# Tractive_System_Board_Rev7_Test.net
KiCad netlist of a schematic drawn in EAGLE
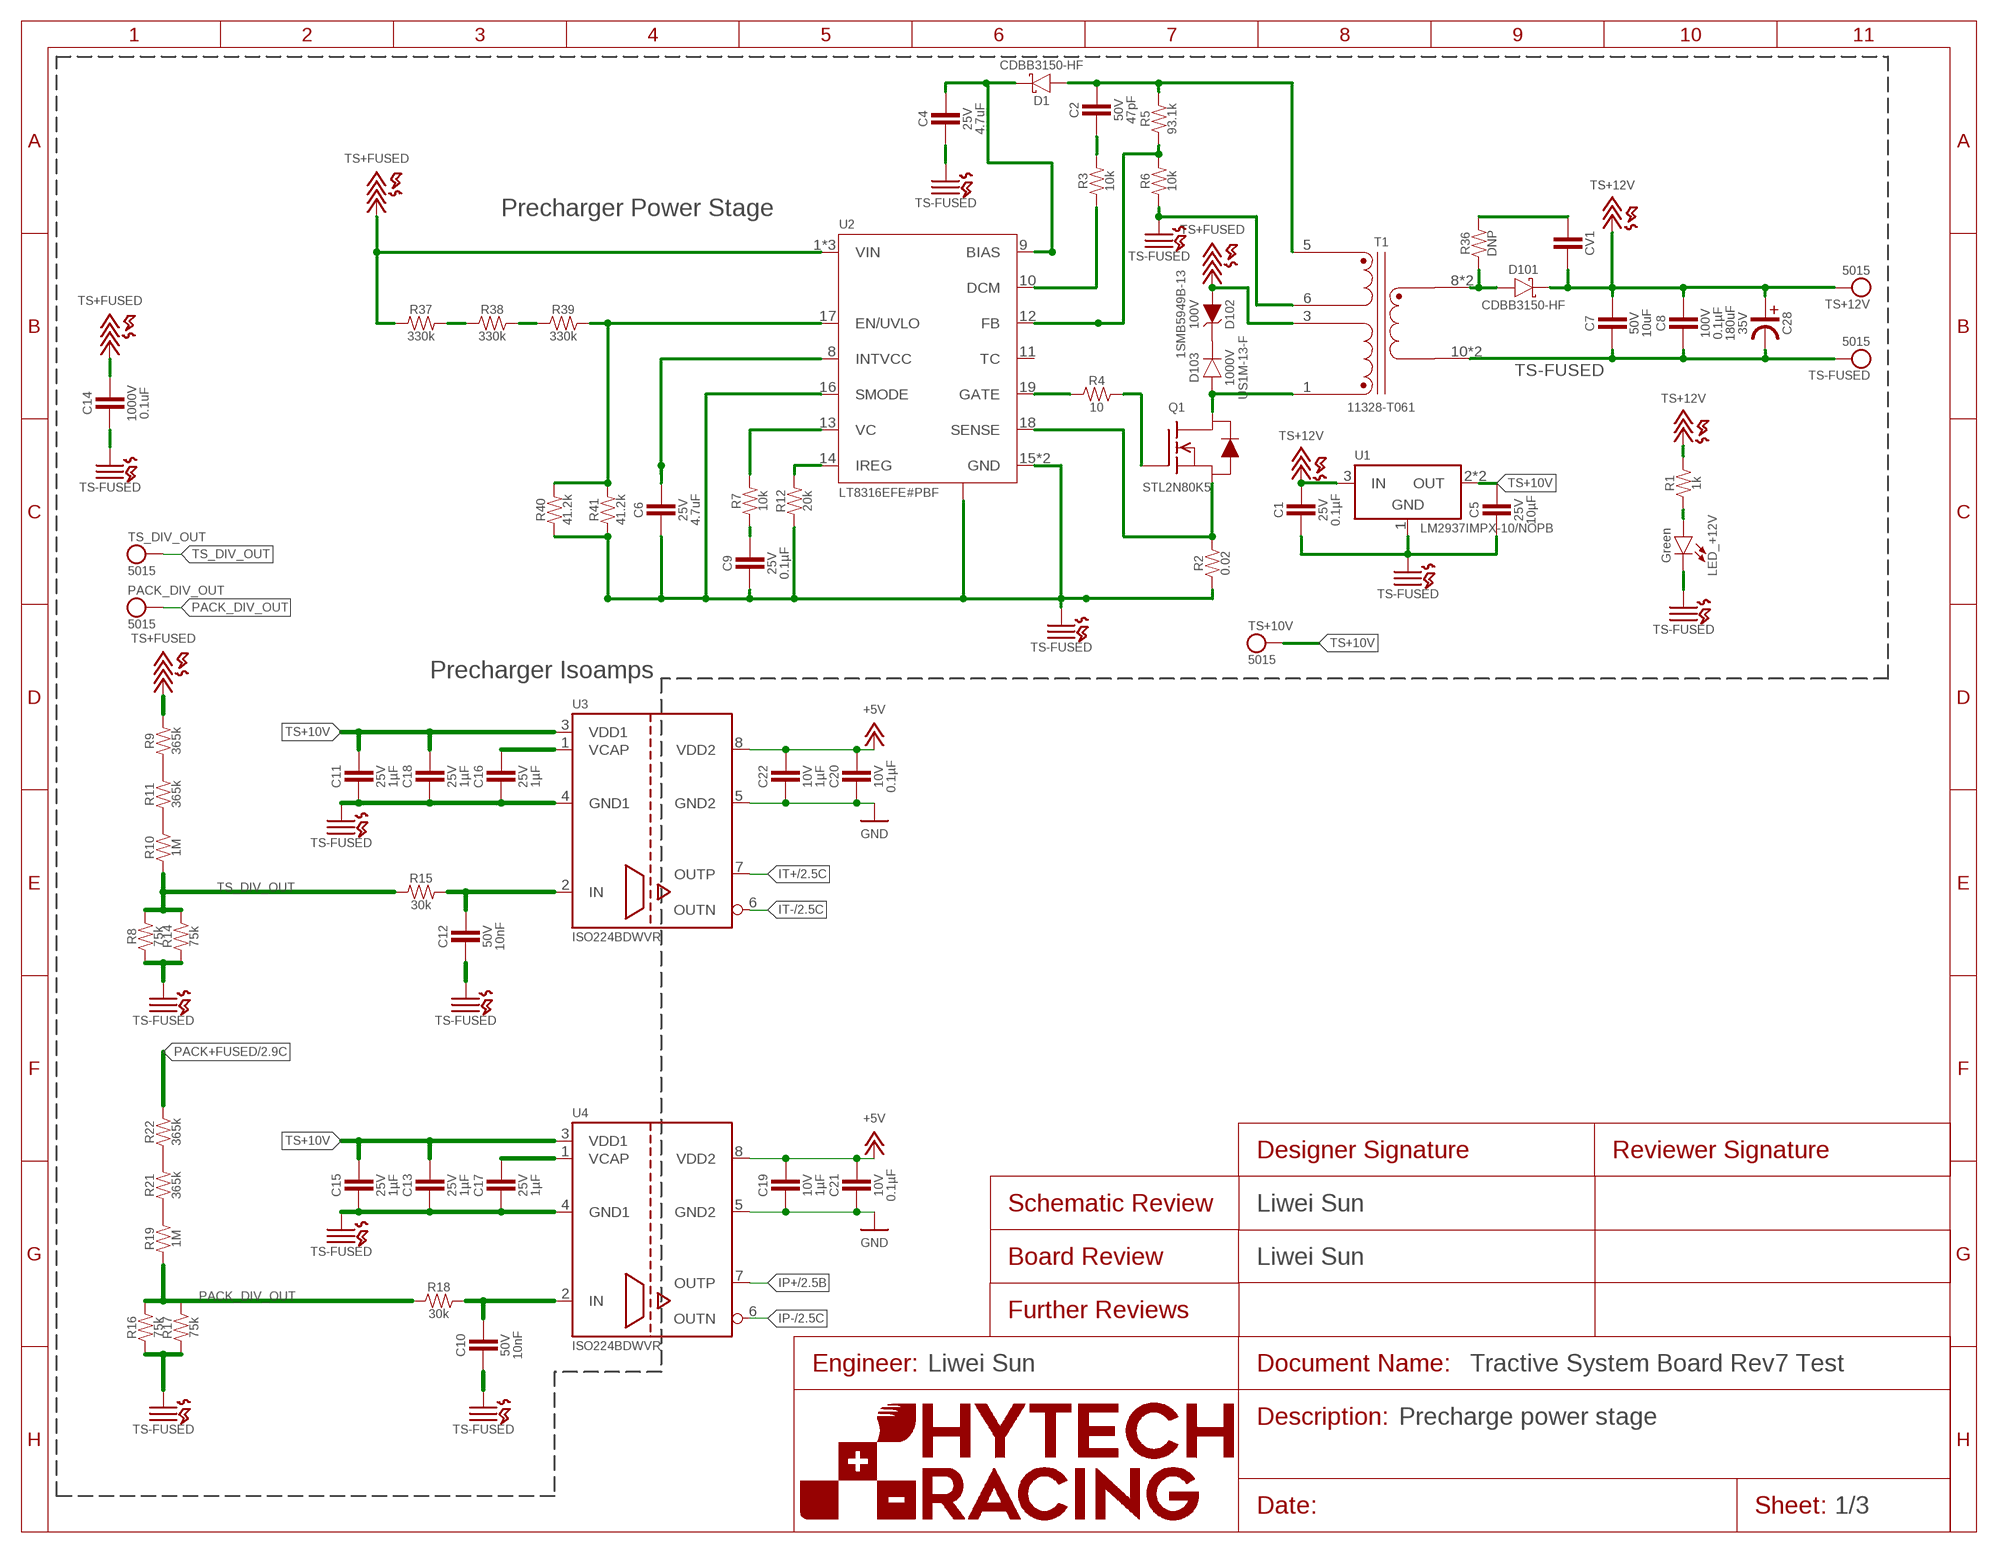
[diagram p0: schematic, sheet 1]
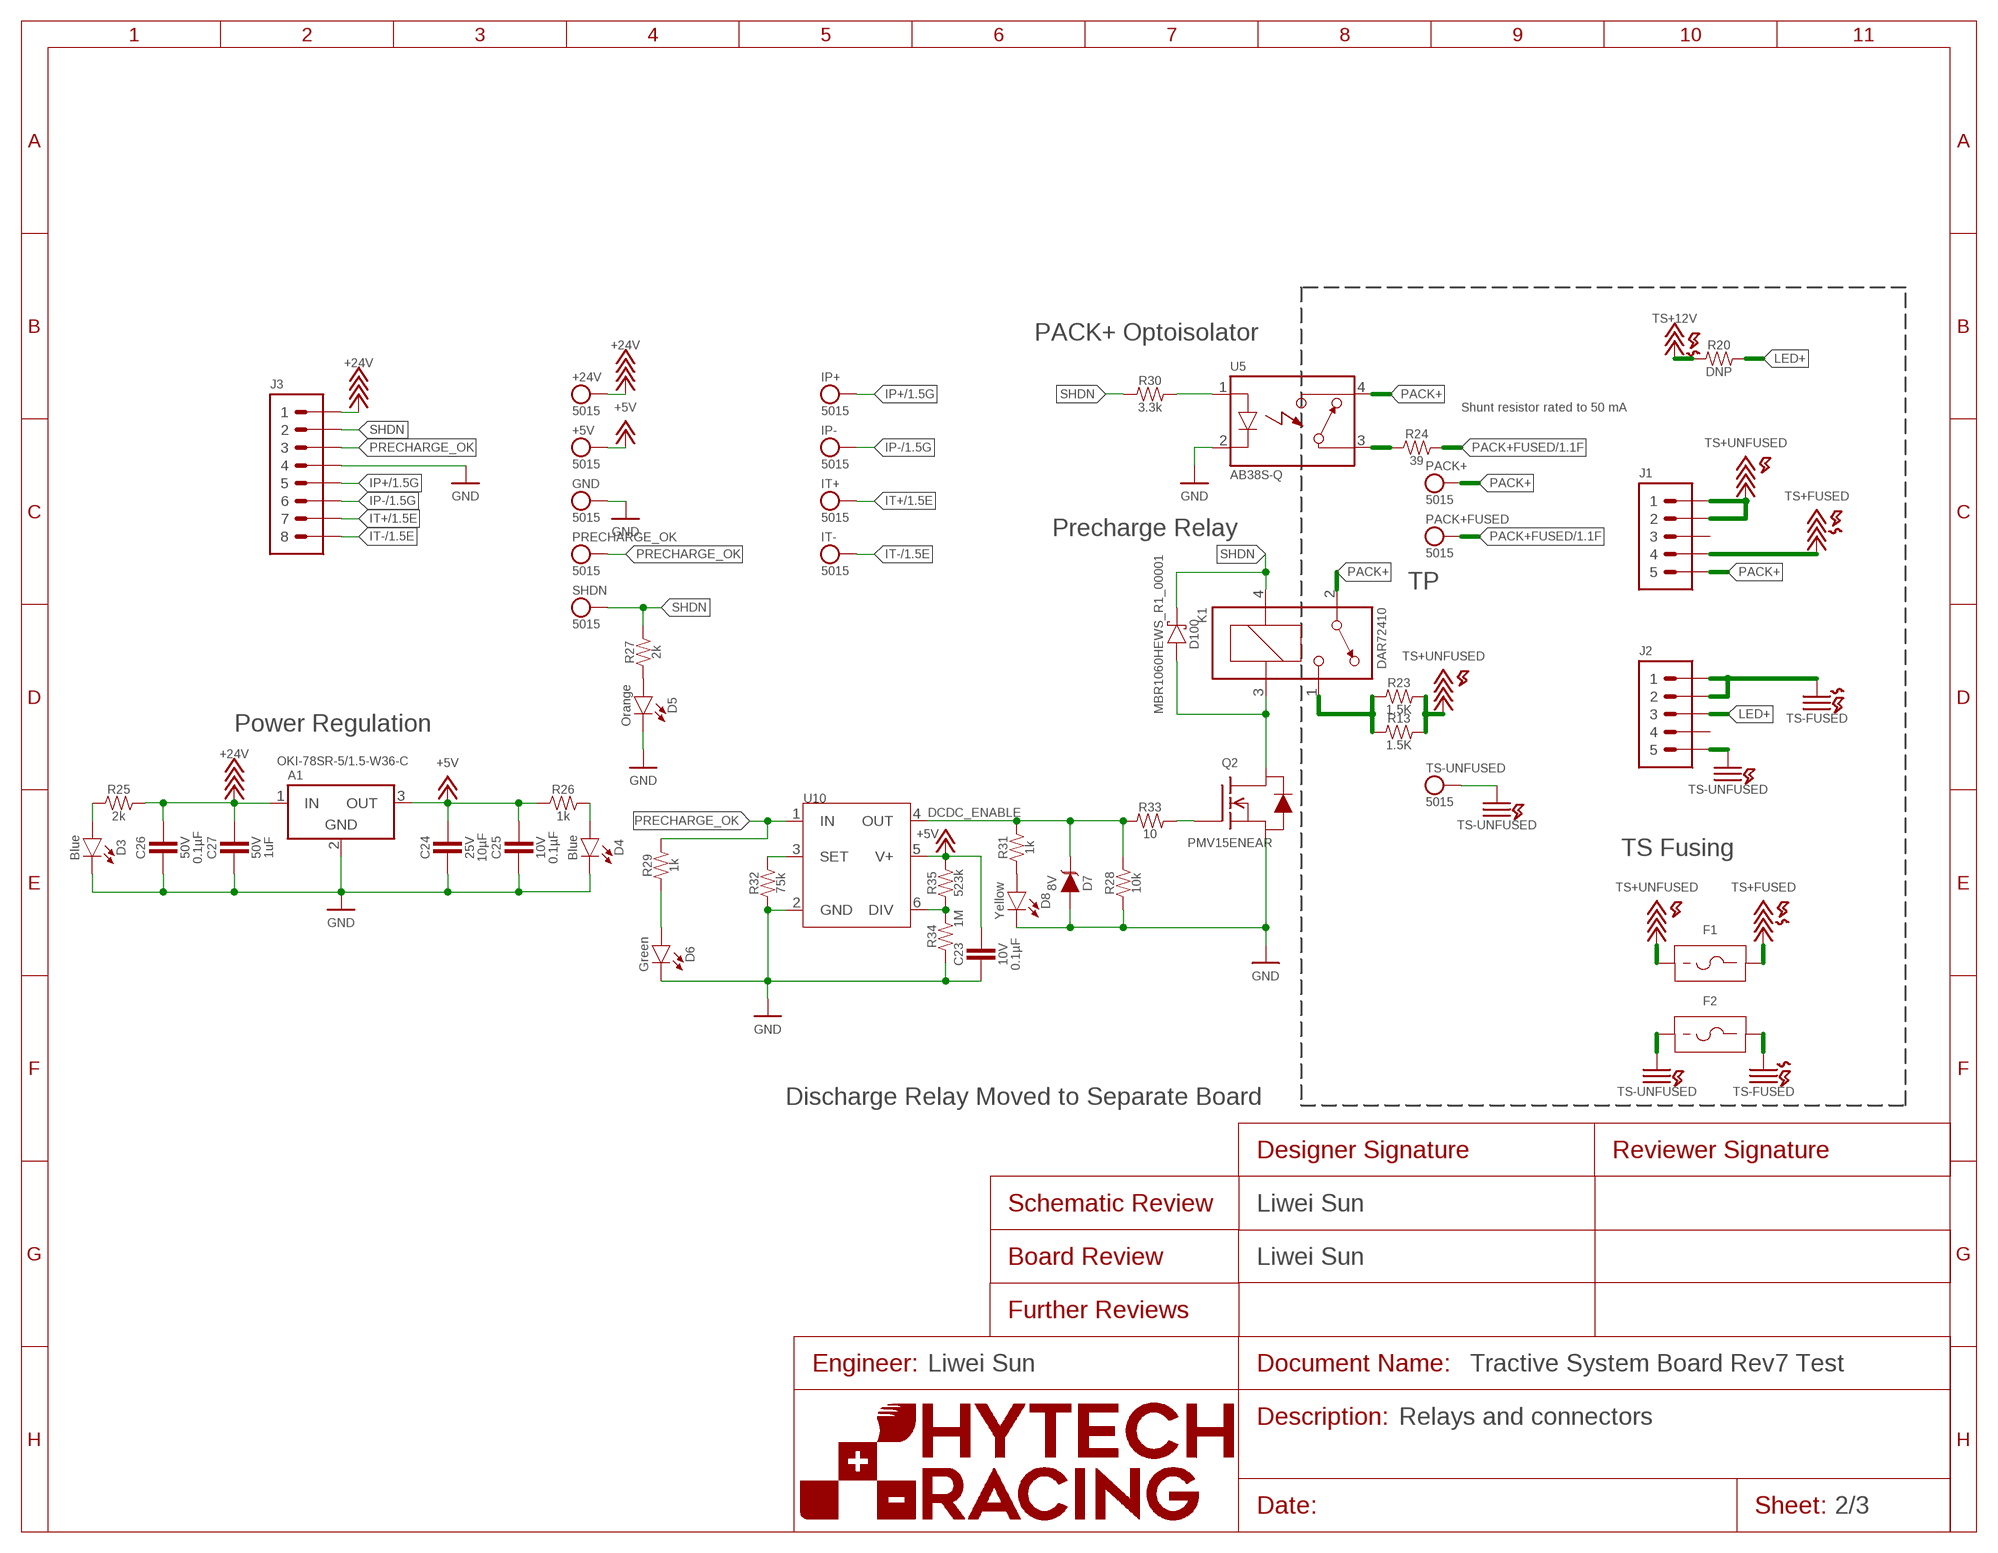
[diagram p1: schematic, sheet 2]
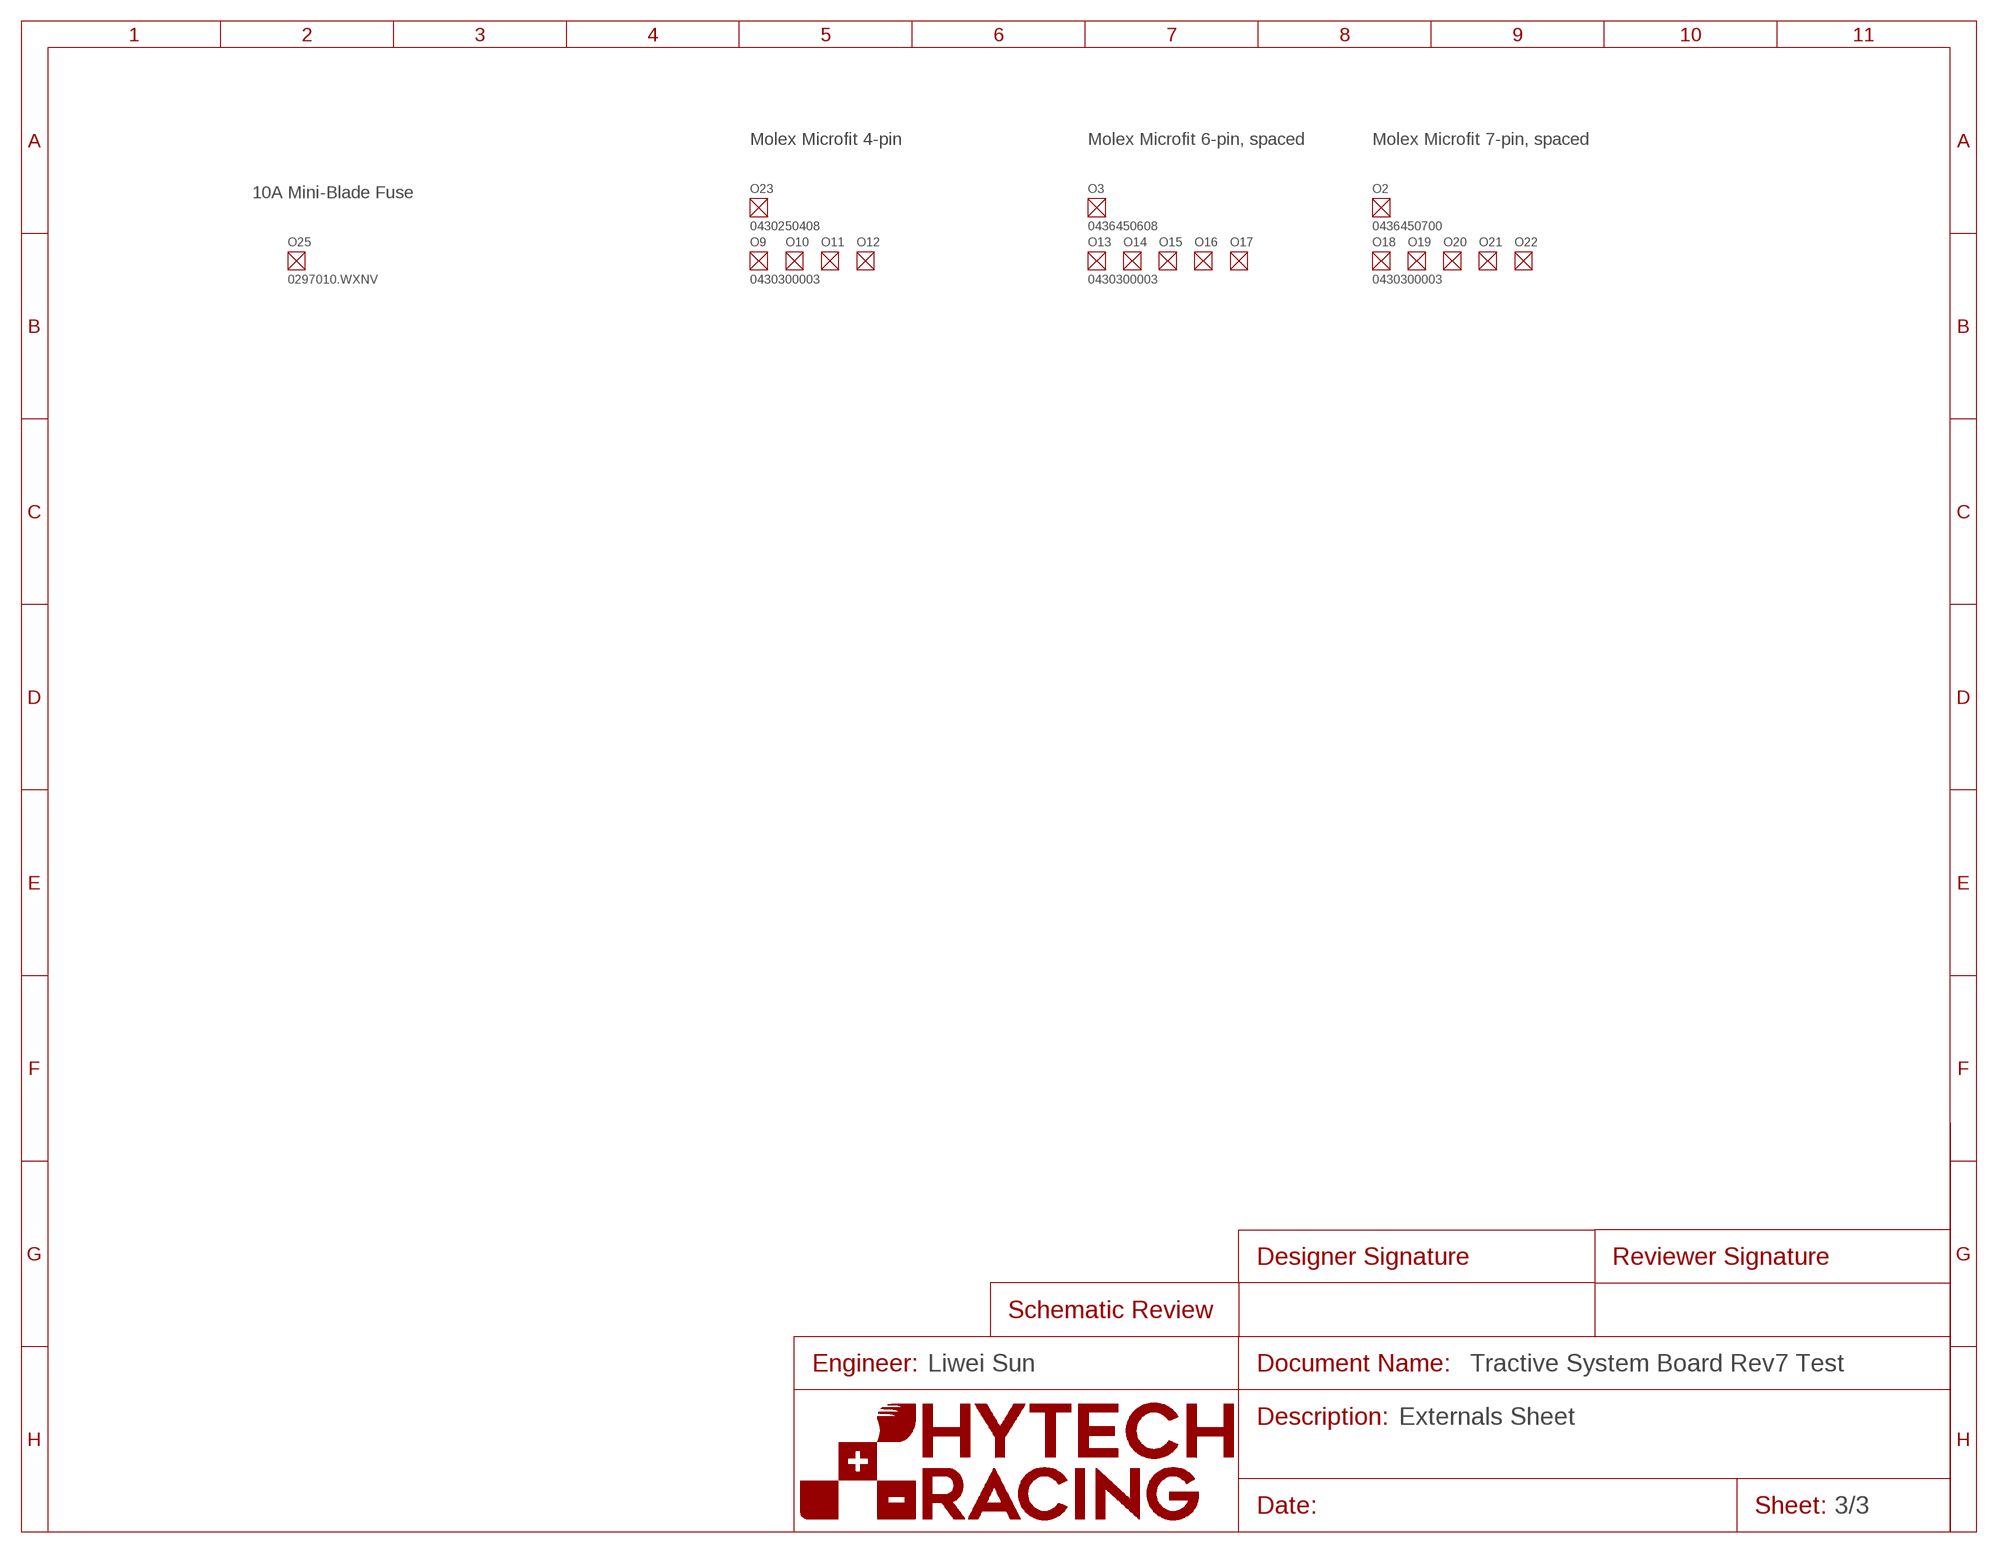
[diagram p2: schematic, sheet 3]

(export (version "E")
  (design (tool "Eeschema 10.0.6"))
  (components
    (comp (ref "+5V")
      (value "TEST_POINT")
      (footprint "eagle-import:5015")
      (fields (field (name "MPN") "5015") (field (name "MANUFACTURER") "Keystone Electronics"))
      (libsource (lib "eagle-import") (part "TEST_POINT"))
    )
    (comp (ref "+24V")
      (value "TEST_POINT")
      (footprint "eagle-import:5015")
      (fields (field (name "MPN") "5015") (field (name "MANUFACTURER") "Keystone Electronics"))
      (libsource (lib "eagle-import") (part "TEST_POINT"))
    )
    (comp (ref "A1")
      (value "VOLTAGE_REGULATOR_MODULE_OKI-78SR_5V")
      (footprint "eagle-import:OKI-78SR")
      (fields
        (field (name "MANUFACTURER") "Murata Power Solutions Inc.")
        (field (name "MPN") "OKI-78SR-5/1.5-W36-C")
      )
      (libsource (lib "eagle-import") (part "VOLTAGE_REGULATOR_MODULE_?_OKI-78SR5V"))
    )
    (comp (ref "C23")
      (value "CAPACITOR_0603_10V_0.1UF")
      (footprint "eagle-import:0603-CAP")
      (fields
        (field (name "CAPACITANCE") "0.1µF")
        (field (name "MANUFACTURER") "Vishay Vitramon")
        (field (name "MPN") "VJ0603Y104JXQPW1BC")
        (field (name "TOLERANCE") "5%")
        (field (name "VOLTAGE") "10V")
      )
      (libsource (lib "eagle-import") (part "CAPACITOR_?_060310V_0.1UF"))
    )
    (comp (ref "C24")
      (value "CAPACITOR_0603_25V_10UF")
      (footprint "eagle-import:0603-CAP")
      (fields
        (field (name "CAPACITANCE") "10µF")
        (field (name "MANUFACTURER") "Murata Electronics")
        (field (name "MPN") "GRM188R61E106MA73D")
        (field (name "TOLERANCE") "20%")
        (field (name "VOLTAGE") "25V")
      )
      (libsource (lib "eagle-import") (part "CAPACITOR_?_060325V_10UF"))
    )
    (comp (ref "C25")
      (value "CAPACITOR_0603_10V_0.1UF")
      (footprint "eagle-import:0603-CAP")
      (fields
        (field (name "CAPACITANCE") "0.1µF")
        (field (name "MANUFACTURER") "Vishay Vitramon")
        (field (name "MPN") "VJ0603Y104JXQPW1BC")
        (field (name "TOLERANCE") "5%")
        (field (name "VOLTAGE") "10V")
      )
      (libsource (lib "eagle-import") (part "CAPACITOR_?_060310V_0.1UF"))
    )
    (comp (ref "C26")
      (value "CAPACITOR_0603_50V_0.1UF")
      (footprint "eagle-import:0603-CAP")
      (fields
        (field (name "CAPACITANCE") "0.1µF")
        (field (name "MANUFACTURER") "Yageo")
        (field (name "MPN") "CC0603KRX7R9BB104")
        (field (name "TOLERANCE") "10%")
        (field (name "VOLTAGE") "50V")
      )
      (libsource (lib "eagle-import") (part "CAPACITOR_?_060350V_0.1UF"))
    )
    (comp (ref "C27")
      (value "CAPACITOR_0603_50V_1UF")
      (footprint "eagle-import:0603-CAP")
      (fields
        (field (name "CAPACITANCE") "1uF")
        (field (name "MANUFACTURER") "Taiyo Yuden")
        (field (name "MPN") "UMK107BJ105KA-T")
        (field (name "TOLERANCE") "10%")
        (field (name "VOLTAGE") "50V")
      )
      (libsource (lib "eagle-import") (part "CAPACITOR_?_060350V_1UF"))
    )
    (comp (ref "D3")
      (value "LED_0603_BLUE")
      (footprint "eagle-import:0603-LED")
      (fields
        (field (name "COLOR") "Blue")
        (field (name "MANUFACTURER") "Kingbright")
        (field (name "MPN") "APT1608VBC/D")
      )
      (libsource (lib "eagle-import") (part "LED_?_0603BLUE"))
    )
    (comp (ref "D4")
      (value "LED_0603_BLUE")
      (footprint "eagle-import:0603-LED")
      (fields
        (field (name "COLOR") "Blue")
        (field (name "MANUFACTURER") "Kingbright")
        (field (name "MPN") "APT1608VBC/D")
      )
      (libsource (lib "eagle-import") (part "LED_?_0603BLUE"))
    )
    (comp (ref "D5")
      (value "LED_0603_ORANGE")
      (footprint "eagle-import:0603-LED")
      (fields
        (field (name "COLOR") "Orange")
        (field (name "MANUFACTURER") "Kingbright")
        (field (name "MPN") "APT1608SECK")
      )
      (libsource (lib "eagle-import") (part "LED_?_0603ORANGE"))
    )
    (comp (ref "D6")
      (value "LED_0603_GREEN")
      (footprint "eagle-import:0603-LED")
      (fields
        (field (name "COLOR") "Green")
        (field (name "MANUFACTURER") "Kingbright")
        (field (name "MPN") "APT1608ZGCK")
      )
      (libsource (lib "eagle-import") (part "LED_?_0603GREEN"))
    )
    (comp (ref "D7")
      (value "TVS__8V")
      (footprint "eagle-import:SOT-23")
      (fields
        (field (name "MANUFACTURER") "Vishay General Semiconductor - Diodes Division")
        (field (name "MPN") "GSOT08-E3-08")
        (field (name "VOLTAGE") "8V")
      )
      (libsource (lib "eagle-import") (part "TVS_?_8V"))
    )
    (comp (ref "D8")
      (value "LED_0603_YELLOW")
      (footprint "eagle-import:0603-LED")
      (fields
        (field (name "COLOR") "Yellow")
        (field (name "MANUFACTURER") "Kingbright")
        (field (name "MPN") "APT1608SYCK/J3-PRV")
      )
      (libsource (lib "eagle-import") (part "LED_?_0603YELLOW"))
    )
    (comp (ref "D100")
      (value "SCHOTTKY_SOD323_60V")
      (footprint "eagle-import:SOD-323")
      (fields
        (field (name "MANUFACTURER") "Panjit International Inc.")
        (field (name "MPN") "MBR1060HEWS_R1_00001")
        (field (name "VOLTAGE") "60V")
      )
      (libsource (lib "eagle-import") (part "SCHOTTKY_?_SOD32360V"))
    )
    (comp (ref "F1")
      (value "FUSE_HOLDER_122")
      (footprint "eagle-import:122")
      (fields (field (name "MPN") "01220088Z") (field (name "MANUFACTURER") "Littelfuse"))
      (libsource (lib "eagle-import") (part "FUSE_HOLDER_122"))
    )
    (comp (ref "F2")
      (value "FUSE_HOLDER_122")
      (footprint "eagle-import:122")
      (fields (field (name "MPN") "01220088Z") (field (name "MANUFACTURER") "Littelfuse"))
      (libsource (lib "eagle-import") (part "FUSE_HOLDER_122"))
    )
    (comp (ref "GND")
      (value "TEST_POINT")
      (footprint "eagle-import:5015")
      (fields (field (name "MPN") "5015") (field (name "MANUFACTURER") "Keystone Electronics"))
      (libsource (lib "eagle-import") (part "TEST_POINT"))
    )
    (comp (ref "IP+")
      (value "TEST_POINT")
      (footprint "eagle-import:5015")
      (fields (field (name "MPN") "5015") (field (name "MANUFACTURER") "Keystone Electronics"))
      (libsource (lib "eagle-import") (part "TEST_POINT"))
    )
    (comp (ref "IP-")
      (value "TEST_POINT")
      (footprint "eagle-import:5015")
      (fields (field (name "MPN") "5015") (field (name "MANUFACTURER") "Keystone Electronics"))
      (libsource (lib "eagle-import") (part "TEST_POINT"))
    )
    (comp (ref "IT+")
      (value "TEST_POINT")
      (footprint "eagle-import:5015")
      (fields (field (name "MPN") "5015") (field (name "MANUFACTURER") "Keystone Electronics"))
      (libsource (lib "eagle-import") (part "TEST_POINT"))
    )
    (comp (ref "IT-")
      (value "TEST_POINT")
      (footprint "eagle-import:5015")
      (fields (field (name "MPN") "5015") (field (name "MANUFACTURER") "Keystone Electronics"))
      (libsource (lib "eagle-import") (part "TEST_POINT"))
    )
    (comp (ref "J1")
      (value "CONNECTOR-5_MICRO_V7S_")
      (footprint "eagle-import:MOLEX_MICROFIT_PTH_VERTICAL_07_SINGLE_SPACED")
      (fields (field (name "MPN") "2165713007") (field (name "MANUFACTURER") "Molex"))
      (libsource (lib "eagle-import") (part "CONNECTOR-5_?_MICRO_V7S"))
    )
    (comp (ref "J2")
      (value "CONNECTOR-5_MICRO_V6S_")
      (footprint "eagle-import:MOLEX_MICROFIT_PTH_VERTICAL_06_SINGLE_SPACED")
      (fields (field (name "MPN") "2165713006") (field (name "MANUFACTURER") "Molex"))
      (libsource (lib "eagle-import") (part "CONNECTOR-5_?_MICRO_V6S"))
    )
    (comp (ref "J3")
      (value "CONNECTOR-8_μF_T_V_BLACK")
      (footprint "eagle-import:MOLEX_MICROFIT_PTH_VERTICAL_08_DUAL")
      (fields (field (name "MANUFACTURER") "Molex") (field (name "MPN") "430450814"))
      (libsource (lib "eagle-import") (part "CONNECTOR-8_?_μF_T_VBLACK"))
    )
    (comp (ref "K1")
      (value "RELAY_SPST_NO_D_24")
      (footprint "eagle-import:D")
      (fields (field (name "MANUFACTURER") "Sensata-Cynergy3") (field (name "MPN") "DAR72410"))
      (libsource (lib "eagle-import") (part "RELAY_SPST_NO_?D_24"))
    )
    (comp (ref "PACK+")
      (value "TEST_POINT")
      (footprint "eagle-import:5015")
      (fields (field (name "MPN") "5015") (field (name "MANUFACTURER") "Keystone Electronics"))
      (libsource (lib "eagle-import") (part "TEST_POINT"))
    )
    (comp (ref "PACK+FUSED")
      (value "TEST_POINT")
      (footprint "eagle-import:5015")
      (fields (field (name "MPN") "5015") (field (name "MANUFACTURER") "Keystone Electronics"))
      (libsource (lib "eagle-import") (part "TEST_POINT"))
    )
    (comp (ref "PRECHARGE_OK")
      (value "TEST_POINT")
      (footprint "eagle-import:5015")
      (fields (field (name "MPN") "5015") (field (name "MANUFACTURER") "Keystone Electronics"))
      (libsource (lib "eagle-import") (part "TEST_POINT"))
    )
    (comp (ref "Q2")
      (value "TRANSISTOR_N_MOS__PMV15ENEA")
      (footprint "eagle-import:SOT-23")
      (fields (field (name "MANUFACTURER") "Nexperia USA Inc.") (field (name "MPN") "PMV15ENEAR"))
      (libsource (lib "eagle-import") (part "TRANSISTOR_N_MOS_?_PMV15ENEA"))
    )
    (comp (ref "R13")
      (value "RESISTOR_B20-SHORTENED_1.5K")
      (footprint "eagle-import:B20-SHORTENED")
      (fields
        (field (name "MANUFACTURER") "Ohmite")
        (field (name "MPN") "B20J1K5E")
        (field (name "POWER") "20W")
        (field (name "RESISTANCE") "1.5K")
      )
      (libsource (lib "eagle-import") (part "RESISTOR_?_B20-SHORTENED1.5K"))
    )
    (comp (ref "R20")
      (value "RESISTOR_0603_DNP")
      (footprint "eagle-import:0603-RES")
      (fields (field (name "RESISTANCE") "DNP"))
      (libsource (lib "eagle-import") (part "RESISTOR_?_0603DNP"))
    )
    (comp (ref "R23")
      (value "RESISTOR_B20-SHORTENED_1.5K")
      (footprint "eagle-import:B20-SHORTENED")
      (fields
        (field (name "MANUFACTURER") "Ohmite")
        (field (name "MPN") "B20J1K5E")
        (field (name "POWER") "20W")
        (field (name "RESISTANCE") "1.5K")
      )
      (libsource (lib "eagle-import") (part "RESISTOR_?_B20-SHORTENED1.5K"))
    )
    (comp (ref "R24")
      (value "RESISTOR_0603_39")
      (footprint "eagle-import:0603-RES")
      (fields
        (field (name "MANUFACTURER") "Yageo")
        (field (name "MPN") "RT0603BRD0739RL")
        (field (name "POWER") "0.1W")
        (field (name "RESISTANCE") "39")
      )
      (libsource (lib "eagle-import") (part "RESISTOR_?_060339"))
    )
    (comp (ref "R25")
      (value "RESISTOR_0603_2K")
      (footprint "eagle-import:0603-RES")
      (fields
        (field (name "MANUFACTURER") "Panasonic Electronic Components")
        (field (name "MPN") "ERJ-UP3F2001V")
        (field (name "POWER") "0.25W")
        (field (name "RESISTANCE") "2k")
      )
      (libsource (lib "eagle-import") (part "RESISTOR_?_06032K"))
    )
    (comp (ref "R26")
      (value "RESISTOR_0603_1K")
      (footprint "eagle-import:0603-RES")
      (fields
        (field (name "MANUFACTURER") "TE Connectivity Passive Product")
        (field (name "MPN") " CPF-A-0603B1K0E")
        (field (name "POWER") "0.0625W")
        (field (name "RESISTANCE") "1k")
      )
      (libsource (lib "eagle-import") (part "RESISTOR_?_06031K"))
    )
    (comp (ref "R27")
      (value "RESISTOR_0603_2K")
      (footprint "eagle-import:0603-RES")
      (fields
        (field (name "MANUFACTURER") "Panasonic Electronic Components")
        (field (name "MPN") "ERJ-UP3F2001V")
        (field (name "POWER") "0.25W")
        (field (name "RESISTANCE") "2k")
      )
      (libsource (lib "eagle-import") (part "RESISTOR_?_06032K"))
    )
    (comp (ref "R28")
      (value "RESISTOR_0603_10K")
      (footprint "eagle-import:0603-RES")
      (fields
        (field (name "MANUFACTURER") "Panasonic Electronic Components")
        (field (name "MPN") "ERA-3ARB103V")
        (field (name "POWER") "0.1W")
        (field (name "RESISTANCE") "10k")
      )
      (libsource (lib "eagle-import") (part "RESISTOR_?_060310K"))
    )
    (comp (ref "R29")
      (value "RESISTOR_0603_1K")
      (footprint "eagle-import:0603-RES")
      (fields
        (field (name "MANUFACTURER") "TE Connectivity Passive Product")
        (field (name "MPN") " CPF-A-0603B1K0E")
        (field (name "POWER") "0.0625W")
        (field (name "RESISTANCE") "1k")
      )
      (libsource (lib "eagle-import") (part "RESISTOR_?_06031K"))
    )
    (comp (ref "R30")
      (value "RESISTOR_0603_3.3K")
      (footprint "eagle-import:0603-RES")
      (fields
        (field (name "MANUFACTURER") "Panasonic Electronic Components")
        (field (name "MPN") "ERJ-PB3D3301V")
        (field (name "POWER") "0.3W")
        (field (name "RESISTANCE") "3.3k")
      )
      (libsource (lib "eagle-import") (part "RESISTOR_?_06033.3K"))
    )
    (comp (ref "R31")
      (value "RESISTOR_0603_1K")
      (footprint "eagle-import:0603-RES")
      (fields
        (field (name "MANUFACTURER") "TE Connectivity Passive Product")
        (field (name "MPN") " CPF-A-0603B1K0E")
        (field (name "POWER") "0.0625W")
        (field (name "RESISTANCE") "1k")
      )
      (libsource (lib "eagle-import") (part "RESISTOR_?_06031K"))
    )
    (comp (ref "R32")
      (value "RESISTOR_0603_75K")
      (footprint "eagle-import:0603-RES")
      (fields
        (field (name "MANUFACTURER") "Yageo")
        (field (name "MPN") "RT0603BRE0775KL")
        (field (name "POWER") "0.1W")
        (field (name "RESISTANCE") "75k")
      )
      (libsource (lib "eagle-import") (part "RESISTOR_?_060375K"))
    )
    (comp (ref "R33")
      (value "RESISTOR_0603_10")
      (footprint "eagle-import:0603-RES")
      (fields
        (field (name "MANUFACTURER") "Yageo")
        (field (name "MPN") "RC0603FR-0710RL")
        (field (name "POWER") "0.1W")
        (field (name "RESISTANCE") "10")
      )
      (libsource (lib "eagle-import") (part "RESISTOR_?_060310"))
    )
    (comp (ref "R34")
      (value "RESISTOR_0805_1M")
      (footprint "eagle-import:0805-RES")
      (fields
        (field (name "MANUFACTURER") "Panasonic Electronic Components")
        (field (name "MPN") "ERJ-PB6B1004V")
        (field (name "POWER") "0.25W")
        (field (name "RESISTANCE") "1M")
      )
      (libsource (lib "eagle-import") (part "RESISTOR_?_08051M"))
    )
    (comp (ref "R35")
      (value "RESISTOR_0805_523K")
      (footprint "eagle-import:0805-RES")
      (fields
        (field (name "MANUFACTURER") "Panasonic Electronic Components")
        (field (name "MPN") "ERJ-PB6B5233V")
        (field (name "POWER") "0.25W")
        (field (name "RESISTANCE") "523k")
      )
      (libsource (lib "eagle-import") (part "RESISTOR_?_0805523K"))
    )
    (comp (ref "SHDN")
      (value "TEST_POINT")
      (footprint "eagle-import:5015")
      (fields (field (name "MPN") "5015") (field (name "MANUFACTURER") "Keystone Electronics"))
      (libsource (lib "eagle-import") (part "TEST_POINT"))
    )
    (comp (ref "TS-UNFUSED")
      (value "TEST_POINT")
      (footprint "eagle-import:5015")
      (fields (field (name "MPN") "5015") (field (name "MANUFACTURER") "Keystone Electronics"))
      (libsource (lib "eagle-import") (part "TEST_POINT"))
    )
    (comp (ref "U5")
      (value "RELAY_SOLIDSTATE_NO_AB38S-Q-AIRGAP")
      (footprint "eagle-import:SOP-04-AIRGAP")
      (fields
        (field (name "MPN") "AB38S-Q")
        (field (name "MANUFACTURER") "Comus International")
        (field (name "VOLTAGE") "600V")
      )
      (libsource (lib "eagle-import") (part "RELAY_SOLIDSTATE_NO_AB38S-Q-AIRGAP"))
    )
    (comp (ref "U10")
      (value "LTC6994-2")
      (footprint "eagle-import:SOT-23-6")
      (libsource (lib "eagle-import") (part "LTC6994-2"))
    )
    (comp (ref "C1")
      (value "CAPACITOR_0603_25V_0.1UF")
      (footprint "eagle-import:0603-CAP")
      (fields
        (field (name "CAPACITANCE") "0.1µF")
        (field (name "MANUFACTURER") "Samsung Electro-Mechanics")
        (field (name "MPN") "CL10B104KA8NNNC")
        (field (name "TOLERANCE") "10%")
        (field (name "VOLTAGE") "25V")
      )
      (libsource (lib "eagle-import") (part "CAPACITOR_?_060325V_0.1UF"))
    )
    (comp (ref "C2")
      (value "CAPACITOR_0603_50V_47PF")
      (footprint "eagle-import:0603-CAP")
      (fields
        (field (name "CAPACITANCE") "47pF")
        (field (name "MANUFACTURER") "TDK Corporation")
        (field (name "MPN") "CGA3E2NP01H470J080AA")
        (field (name "TOLERANCE") "5%")
        (field (name "VOLTAGE") "50V")
      )
      (libsource (lib "eagle-import") (part "CAPACITOR_?_060350V_47PF"))
    )
    (comp (ref "C4")
      (value "CAPACITOR_0603_25V_4.7UF")
      (footprint "eagle-import:0603-CAP")
      (fields
        (field (name "CAPACITANCE") "4.7uF")
        (field (name "MANUFACTURER") "TDK Corporation")
        (field (name "MPN") " C1608X5R1E475K080AC")
        (field (name "TOLERANCE") "10%")
        (field (name "VOLTAGE") "25V")
      )
      (libsource (lib "eagle-import") (part "CAPACITOR_?_060325V_4.7UF"))
    )
    (comp (ref "C5")
      (value "CAPACITOR_0603_25V_10UF")
      (footprint "eagle-import:0603-CAP")
      (fields
        (field (name "CAPACITANCE") "10µF")
        (field (name "MANUFACTURER") "Murata Electronics")
        (field (name "MPN") "GRM188R61E106MA73D")
        (field (name "TOLERANCE") "20%")
        (field (name "VOLTAGE") "25V")
      )
      (libsource (lib "eagle-import") (part "CAPACITOR_?_060325V_10UF"))
    )
    (comp (ref "C6")
      (value "CAPACITOR_0603_25V_4.7UF")
      (footprint "eagle-import:0603-CAP")
      (fields
        (field (name "CAPACITANCE") "4.7uF")
        (field (name "MANUFACTURER") "TDK Corporation")
        (field (name "MPN") " C1608X5R1E475K080AC")
        (field (name "TOLERANCE") "10%")
        (field (name "VOLTAGE") "25V")
      )
      (libsource (lib "eagle-import") (part "CAPACITOR_?_060325V_4.7UF"))
    )
    (comp (ref "C7")
      (value "CAPACITOR_0805_50V_10UF")
      (footprint "eagle-import:0805-CAP")
      (fields
        (field (name "CAPACITANCE") "10uF")
        (field (name "MANUFACTURER") "Murata")
        (field (name "MPN") " GRM21BR61H106KE43L")
        (field (name "TOLERANCE") "10%")
        (field (name "VOLTAGE") "50V")
      )
      (libsource (lib "eagle-import") (part "CAPACITOR_?_080550V_10UF"))
    )
    (comp (ref "C8")
      (value "CAPACITOR_0603_100V_0.1UF")
      (footprint "eagle-import:0603-CAP")
      (fields
        (field (name "CAPACITANCE") "0.1µF")
        (field (name "MANUFACTURER") "Yageo")
        (field (name "MPN") "CC0603KRX7R0BB104")
        (field (name "TOLERANCE") "10%")
        (field (name "VOLTAGE") "100V")
      )
      (libsource (lib "eagle-import") (part "CAPACITOR_?_0603100V_0.1UF"))
    )
    (comp (ref "C9")
      (value "CAPACITOR_0603_25V_0.1UF")
      (footprint "eagle-import:0603-CAP")
      (fields
        (field (name "CAPACITANCE") "0.1µF")
        (field (name "MANUFACTURER") "Samsung Electro-Mechanics")
        (field (name "MPN") "CL10B104KA8NNNC")
        (field (name "TOLERANCE") "10%")
        (field (name "VOLTAGE") "25V")
      )
      (libsource (lib "eagle-import") (part "CAPACITOR_?_060325V_0.1UF"))
    )
    (comp (ref "C10")
      (value "CAPACITOR_0603_50V_10NF")
      (footprint "eagle-import:0603-CAP")
      (fields
        (field (name "CAPACITANCE") "10nF")
        (field (name "MANUFACTURER") "TDK Corporation")
        (field (name "MPN") "C1608C0G1H103J080AA")
        (field (name "TOLERANCE") "5%")
        (field (name "VOLTAGE") "50V")
      )
      (libsource (lib "eagle-import") (part "CAPACITOR_?_060350V_10NF"))
    )
    (comp (ref "C11")
      (value "CAPACITOR_0603_25V_1UF")
      (footprint "eagle-import:0603-CAP")
      (fields
        (field (name "CAPACITANCE") "1µF")
        (field (name "MANUFACTURER") "Samsung Electro-Mechanics")
        (field (name "MPN") "CL10B105KA8NNNC")
        (field (name "TOLERANCE") "10%")
        (field (name "VOLTAGE") "25V")
      )
      (libsource (lib "eagle-import") (part "CAPACITOR_?_060325V_1UF"))
    )
    (comp (ref "C12")
      (value "CAPACITOR_0603_50V_10NF")
      (footprint "eagle-import:0603-CAP")
      (fields
        (field (name "CAPACITANCE") "10nF")
        (field (name "MANUFACTURER") "TDK Corporation")
        (field (name "MPN") "C1608C0G1H103J080AA")
        (field (name "TOLERANCE") "5%")
        (field (name "VOLTAGE") "50V")
      )
      (libsource (lib "eagle-import") (part "CAPACITOR_?_060350V_10NF"))
    )
    (comp (ref "C13")
      (value "CAPACITOR_0603_25V_1UF")
      (footprint "eagle-import:0603-CAP")
      (fields
        (field (name "CAPACITANCE") "1µF")
        (field (name "MANUFACTURER") "Samsung Electro-Mechanics")
        (field (name "MPN") "CL10B105KA8NNNC")
        (field (name "TOLERANCE") "10%")
        (field (name "VOLTAGE") "25V")
      )
      (libsource (lib "eagle-import") (part "CAPACITOR_?_060325V_1UF"))
    )
    (comp (ref "C14")
      (value "CAPACITOR_1812_1000V_0.1UF")
      (footprint "eagle-import:1812-CAP")
      (fields
        (field (name "CAPACITANCE") "0.1uF")
        (field (name "MANUFACTURER") "KEMET")
        (field (name "MPN") "C1812W104KDRAC7800")
        (field (name "TOLERANCE") "10%")
        (field (name "VOLTAGE") "1000V")
      )
      (libsource (lib "eagle-import") (part "CAPACITOR_?_18121000V_0.1UF"))
    )
    (comp (ref "C15")
      (value "CAPACITOR_0603_25V_1UF")
      (footprint "eagle-import:0603-CAP")
      (fields
        (field (name "CAPACITANCE") "1µF")
        (field (name "MANUFACTURER") "Samsung Electro-Mechanics")
        (field (name "MPN") "CL10B105KA8NNNC")
        (field (name "TOLERANCE") "10%")
        (field (name "VOLTAGE") "25V")
      )
      (libsource (lib "eagle-import") (part "CAPACITOR_?_060325V_1UF"))
    )
    (comp (ref "C16")
      (value "CAPACITOR_0603_25V_1UF")
      (footprint "eagle-import:0603-CAP")
      (fields
        (field (name "CAPACITANCE") "1µF")
        (field (name "MANUFACTURER") "Samsung Electro-Mechanics")
        (field (name "MPN") "CL10B105KA8NNNC")
        (field (name "TOLERANCE") "10%")
        (field (name "VOLTAGE") "25V")
      )
      (libsource (lib "eagle-import") (part "CAPACITOR_?_060325V_1UF"))
    )
    (comp (ref "C17")
      (value "CAPACITOR_0603_25V_1UF")
      (footprint "eagle-import:0603-CAP")
      (fields
        (field (name "CAPACITANCE") "1µF")
        (field (name "MANUFACTURER") "Samsung Electro-Mechanics")
        (field (name "MPN") "CL10B105KA8NNNC")
        (field (name "TOLERANCE") "10%")
        (field (name "VOLTAGE") "25V")
      )
      (libsource (lib "eagle-import") (part "CAPACITOR_?_060325V_1UF"))
    )
    (comp (ref "C18")
      (value "CAPACITOR_0603_25V_1UF")
      (footprint "eagle-import:0603-CAP")
      (fields
        (field (name "CAPACITANCE") "1µF")
        (field (name "MANUFACTURER") "Samsung Electro-Mechanics")
        (field (name "MPN") "CL10B105KA8NNNC")
        (field (name "TOLERANCE") "10%")
        (field (name "VOLTAGE") "25V")
      )
      (libsource (lib "eagle-import") (part "CAPACITOR_?_060325V_1UF"))
    )
    (comp (ref "C19")
      (value "CAPACITOR_0603_10V_1UF")
      (footprint "eagle-import:0603-CAP")
      (fields
        (field (name "CAPACITANCE") "1µF")
        (field (name "MANUFACTURER") "Yageo")
        (field (name "MPN") "CC0603KRX7R6BB105")
        (field (name "TOLERANCE") "10%")
        (field (name "VOLTAGE") "10V")
      )
      (libsource (lib "eagle-import") (part "CAPACITOR_?_060310V_1UF"))
    )
    (comp (ref "C20")
      (value "CAPACITOR_0603_10V_0.1UF")
      (footprint "eagle-import:0603-CAP")
      (fields
        (field (name "CAPACITANCE") "0.1µF")
        (field (name "MANUFACTURER") "Vishay Vitramon")
        (field (name "MPN") "VJ0603Y104JXQPW1BC")
        (field (name "TOLERANCE") "5%")
        (field (name "VOLTAGE") "10V")
      )
      (libsource (lib "eagle-import") (part "CAPACITOR_?_060310V_0.1UF"))
    )
    (comp (ref "C21")
      (value "CAPACITOR_0603_10V_0.1UF")
      (footprint "eagle-import:0603-CAP")
      (fields
        (field (name "CAPACITANCE") "0.1µF")
        (field (name "MANUFACTURER") "Vishay Vitramon")
        (field (name "MPN") "VJ0603Y104JXQPW1BC")
        (field (name "TOLERANCE") "5%")
        (field (name "VOLTAGE") "10V")
      )
      (libsource (lib "eagle-import") (part "CAPACITOR_?_060310V_0.1UF"))
    )
    (comp (ref "C22")
      (value "CAPACITOR_0603_10V_1UF")
      (footprint "eagle-import:0603-CAP")
      (fields
        (field (name "CAPACITANCE") "1µF")
        (field (name "MANUFACTURER") "Yageo")
        (field (name "MPN") "CC0603KRX7R6BB105")
        (field (name "TOLERANCE") "10%")
        (field (name "VOLTAGE") "10V")
      )
      (libsource (lib "eagle-import") (part "CAPACITOR_?_060310V_1UF"))
    )
    (comp (ref "C28")
      (value "CAPACITOR_ELECTROLYTIC_A759KR_180UF")
      (footprint "eagle-import:A759KR")
      (fields
        (field (name "CAPACITANCE") "180uF")
        (field (name "MANUFACTURER") "KEMET")
        (field (name "MPN") "A759KR187M1VAAE024")
        (field (name "TOLERANCE") "20%")
        (field (name "VOLTAGE") "35V")
      )
      (libsource (lib "eagle-import") (part "CAPACITOR_ELECTROLYTIC_?_A759KR180UF"))
    )
    (comp (ref "CV1")
      (value "CAPACITOR_VALUE")
      (footprint "eagle-import:0603-CAP")
      (libsource (lib "eagle-import") (part "CAPACITOR_VALUE"))
    )
    (comp (ref "D1")
      (value "SCHOTTKY_DO-214AA_150V")
      (footprint "eagle-import:DO-214AA")
      (fields
        (field (name "MANUFACTURER") "Comchip Technology")
        (field (name "MPN") "CDBB3150-HF")
        (field (name "VOLTAGE") "150V")
      )
      (libsource (lib "eagle-import") (part "SCHOTTKY_?_DO-214AA150V"))
    )
    (comp (ref "D101")
      (value "SCHOTTKY_DO-214AA_150V")
      (footprint "eagle-import:DO-214AA")
      (fields
        (field (name "MANUFACTURER") "Comchip Technology")
        (field (name "MPN") "CDBB3150-HF")
        (field (name "VOLTAGE") "150V")
      )
      (libsource (lib "eagle-import") (part "SCHOTTKY_?_DO-214AA150V"))
    )
    (comp (ref "D102")
      (value "ZENER_DO-214AA_100V")
      (footprint "eagle-import:DO-214AA")
      (fields
        (field (name "MANUFACTURER") "Diodes Incorporated")
        (field (name "MPN") "1SMB5949B-13")
        (field (name "VOLTAGE") "100V")
      )
      (libsource (lib "eagle-import") (part "ZENER_?_DO-214AA100V"))
    )
    (comp (ref "D103")
      (value "RECTIFIER_1000V_SMA")
      (footprint "eagle-import:SMA")
      (fields
        (field (name "MANUFACTURER") "Diodes Incorporated")
        (field (name "MPN") "US1M-13-F")
        (field (name "VOLTAGE") "1000V")
      )
      (libsource (lib "eagle-import") (part "RECTIFIER__?SMA1000V"))
    )
    (comp (ref "LED_+12V")
      (value "LED_0603_GREEN")
      (footprint "eagle-import:0603-LED")
      (fields
        (field (name "COLOR") "Green")
        (field (name "MANUFACTURER") "Kingbright")
        (field (name "MPN") "APT1608ZGCK")
      )
      (libsource (lib "eagle-import") (part "LED_?_0603GREEN"))
    )
    (comp (ref "PACK_DIV_OUT")
      (value "TEST_POINT")
      (footprint "eagle-import:5015")
      (fields (field (name "MPN") "5015") (field (name "MANUFACTURER") "Keystone Electronics"))
      (libsource (lib "eagle-import") (part "TEST_POINT"))
    )
    (comp (ref "Q1")
      (value "TRANSISTOR_N_MOS_POWERFLAT5X6_STL2N80K5")
      (footprint "eagle-import:POWERFLAT5X6")
      (fields (field (name "MANUFACTURER") "STMicroelectronics") (field (name "MPN") "STL2N80K5"))
      (libsource (lib "eagle-import") (part "TRANSISTOR_N_MOS_?_POWERFLAT5X6STL2N80K5"))
    )
    (comp (ref "R1")
      (value "RESISTOR_0603_1K")
      (footprint "eagle-import:0603-RES")
      (fields
        (field (name "MANUFACTURER") "TE Connectivity Passive Product")
        (field (name "MPN") " CPF-A-0603B1K0E")
        (field (name "POWER") "0.0625W")
        (field (name "RESISTANCE") "1k")
      )
      (libsource (lib "eagle-import") (part "RESISTOR_?_06031K"))
    )
    (comp (ref "R2")
      (value "RESISTOR_0603_0.02")
      (footprint "eagle-import:0603-RES")
      (fields
        (field (name "MANUFACTURER") "Panasonic Electronic Components")
        (field (name "MPN") "ERJ-3BWFR020V")
        (field (name "POWER") "0.33W")
        (field (name "RESISTANCE") "0.02")
      )
      (libsource (lib "eagle-import") (part "RESISTOR_?_06030.02"))
    )
    (comp (ref "R3")
      (value "RESISTOR_0603_10K")
      (footprint "eagle-import:0603-RES")
      (fields
        (field (name "MANUFACTURER") "Panasonic Electronic Components")
        (field (name "MPN") "ERA-3ARB103V")
        (field (name "POWER") "0.1W")
        (field (name "RESISTANCE") "10k")
      )
      (libsource (lib "eagle-import") (part "RESISTOR_?_060310K"))
    )
    (comp (ref "R4")
      (value "RESISTOR_0603_10")
      (footprint "eagle-import:0603-RES")
      (fields
        (field (name "MANUFACTURER") "Yageo")
        (field (name "MPN") "RC0603FR-0710RL")
        (field (name "POWER") "0.1W")
        (field (name "RESISTANCE") "10")
      )
      (libsource (lib "eagle-import") (part "RESISTOR_?_060310"))
    )
    (comp (ref "R5")
      (value "RESISTOR_0603_93.1K")
      (footprint "eagle-import:0603-RES")
      (fields
        (field (name "MANUFACTURER") "Panasonic Electronic Components")
        (field (name "MPN") "ERJ-PB3B9312V")
        (field (name "POWER") "0.2W")
        (field (name "RESISTANCE") "93.1k")
      )
      (libsource (lib "eagle-import") (part "RESISTOR_?_060393.1K"))
    )
    (comp (ref "R6")
      (value "RESISTOR_0603_10K")
      (footprint "eagle-import:0603-RES")
      (fields
        (field (name "MANUFACTURER") "Panasonic Electronic Components")
        (field (name "MPN") "ERA-3ARB103V")
        (field (name "POWER") "0.1W")
        (field (name "RESISTANCE") "10k")
      )
      (libsource (lib "eagle-import") (part "RESISTOR_?_060310K"))
    )
    (comp (ref "R7")
      (value "RESISTOR_0603_10K")
      (footprint "eagle-import:0603-RES")
      (fields
        (field (name "MANUFACTURER") "Panasonic Electronic Components")
        (field (name "MPN") "ERA-3ARB103V")
        (field (name "POWER") "0.1W")
        (field (name "RESISTANCE") "10k")
      )
      (libsource (lib "eagle-import") (part "RESISTOR_?_060310K"))
    )
    (comp (ref "R8")
      (value "RESISTOR_0805_HV75K")
      (footprint "eagle-import:0805-RES")
      (fields
        (field (name "MANUFACTURER") "Rohm Semiconductor")
        (field (name "MPN") "KTR10EZPF7502 ")
        (field (name "POWER") "0.125W")
        (field (name "RESISTANCE") "75k")
      )
      (libsource (lib "eagle-import") (part "RESISTOR_?_0805HV75K"))
    )
    (comp (ref "R9")
      (value "RESISTOR_0805_HV365K")
      (footprint "eagle-import:0805-RES")
      (fields
        (field (name "MANUFACTURER") "Rohm")
        (field (name "MPN") "KTR10EZPF3653")
        (field (name "POWER") "0.125W")
        (field (name "RESISTANCE") "365k")
      )
      (libsource (lib "eagle-import") (part "RESISTOR_?_0805HV365K"))
    )
    (comp (ref "R10")
      (value "RESISTOR_0805_HV1M")
      (footprint "eagle-import:0805-RES")
      (fields
        (field (name "MANUFACTURER") "Rohm Semiconductor")
        (field (name "MPN") "KTR10EZPF1004")
        (field (name "POWER") "0.125W")
        (field (name "RESISTANCE") "1M")
      )
      (libsource (lib "eagle-import") (part "RESISTOR_?_0805HV1M"))
    )
    (comp (ref "R11")
      (value "RESISTOR_0805_HV365K")
      (footprint "eagle-import:0805-RES")
      (fields
        (field (name "MANUFACTURER") "Rohm")
        (field (name "MPN") "KTR10EZPF3653")
        (field (name "POWER") "0.125W")
        (field (name "RESISTANCE") "365k")
      )
      (libsource (lib "eagle-import") (part "RESISTOR_?_0805HV365K"))
    )
    (comp (ref "R12")
      (value "RESISTOR_0603_20K")
      (footprint "eagle-import:0603-RES")
      (fields
        (field (name "MANUFACTURER") "Yageo")
        (field (name "MPN") "RC0603FR-0720KL")
        (field (name "POWER") "0.1 W")
        (field (name "RESISTANCE") "20k")
      )
      (libsource (lib "eagle-import") (part "RESISTOR_?_060320K"))
    )
    (comp (ref "R14")
      (value "RESISTOR_0805_HV75K")
      (footprint "eagle-import:0805-RES")
      (fields
        (field (name "MANUFACTURER") "Rohm Semiconductor")
        (field (name "MPN") "KTR10EZPF7502 ")
        (field (name "POWER") "0.125W")
        (field (name "RESISTANCE") "75k")
      )
      (libsource (lib "eagle-import") (part "RESISTOR_?_0805HV75K"))
    )
    (comp (ref "R15")
      (value "RESISTOR_0603_")
      (footprint "eagle-import:0603-RES")
      (fields
        (field (name "MANUFACTURER") "Panasonic Electronic Components")
        (field (name "MPN") "ERA-3ARB303V")
        (field (name "POWER") "0.1W")
        (field (name "RESISTANCE") "30k")
      )
      (libsource (lib "eagle-import") (part "RESISTOR_?_060330K"))
    )
    (comp (ref "R16")
      (value "RESISTOR_0805_HV75K")
      (footprint "eagle-import:0805-RES")
      (fields
        (field (name "MANUFACTURER") "Rohm Semiconductor")
        (field (name "MPN") "KTR10EZPF7502 ")
        (field (name "POWER") "0.125W")
        (field (name "RESISTANCE") "75k")
      )
      (libsource (lib "eagle-import") (part "RESISTOR_?_0805HV75K"))
    )
    (comp (ref "R17")
      (value "RESISTOR_0805_HV75K")
      (footprint "eagle-import:0805-RES")
      (fields
        (field (name "MANUFACTURER") "Rohm Semiconductor")
        (field (name "MPN") "KTR10EZPF7502 ")
        (field (name "POWER") "0.125W")
        (field (name "RESISTANCE") "75k")
      )
      (libsource (lib "eagle-import") (part "RESISTOR_?_0805HV75K"))
    )
    (comp (ref "R18")
      (value "RESISTOR_0603_")
      (footprint "eagle-import:0603-RES")
      (fields
        (field (name "MANUFACTURER") "Panasonic Electronic Components")
        (field (name "MPN") "ERA-3ARB303V")
        (field (name "POWER") "0.1W")
        (field (name "RESISTANCE") "30k")
      )
      (libsource (lib "eagle-import") (part "RESISTOR_?_060330K"))
    )
    (comp (ref "R19")
      (value "RESISTOR_0805_HV1M")
      (footprint "eagle-import:0805-RES")
      (fields
        (field (name "MANUFACTURER") "Rohm Semiconductor")
        (field (name "MPN") "KTR10EZPF1004")
        (field (name "POWER") "0.125W")
        (field (name "RESISTANCE") "1M")
      )
      (libsource (lib "eagle-import") (part "RESISTOR_?_0805HV1M"))
    )
    (comp (ref "R21")
      (value "RESISTOR_0805_HV365K")
      (footprint "eagle-import:0805-RES")
      (fields
        (field (name "MANUFACTURER") "Rohm")
        (field (name "MPN") "KTR10EZPF3653")
        (field (name "POWER") "0.125W")
        (field (name "RESISTANCE") "365k")
      )
      (libsource (lib "eagle-import") (part "RESISTOR_?_0805HV365K"))
    )
    (comp (ref "R22")
      (value "RESISTOR_0805_HV365K")
      (footprint "eagle-import:0805-RES")
      (fields
        (field (name "MANUFACTURER") "Rohm")
        (field (name "MPN") "KTR10EZPF3653")
        (field (name "POWER") "0.125W")
        (field (name "RESISTANCE") "365k")
      )
      (libsource (lib "eagle-import") (part "RESISTOR_?_0805HV365K"))
    )
    (comp (ref "R36")
      (value "RESISTOR_0603_DNP")
      (footprint "eagle-import:0603-RES")
      (fields (field (name "RESISTANCE") "DNP"))
      (libsource (lib "eagle-import") (part "RESISTOR_?_0603DNP"))
    )
    (comp (ref "R37")
      (value "RESISTOR_0805_HV330K")
      (footprint "eagle-import:0805-RES")
      (fields
        (field (name "MANUFACTURER") "Rohm Semiconductor")
        (field (name "MPN") "KTR10EZPF3303")
        (field (name "POWER") "0.125W")
        (field (name "RESISTANCE") "330k")
      )
      (libsource (lib "eagle-import") (part "RESISTOR_?_0805HV330K"))
    )
    (comp (ref "R38")
      (value "RESISTOR_0805_HV330K")
      (footprint "eagle-import:0805-RES")
      (fields
        (field (name "MANUFACTURER") "Rohm Semiconductor")
        (field (name "MPN") "KTR10EZPF3303")
        (field (name "POWER") "0.125W")
        (field (name "RESISTANCE") "330k")
      )
      (libsource (lib "eagle-import") (part "RESISTOR_?_0805HV330K"))
    )
    (comp (ref "R39")
      (value "RESISTOR_0805_HV330K")
      (footprint "eagle-import:0805-RES")
      (fields
        (field (name "MANUFACTURER") "Rohm Semiconductor")
        (field (name "MPN") "KTR10EZPF3303")
        (field (name "POWER") "0.125W")
        (field (name "RESISTANCE") "330k")
      )
      (libsource (lib "eagle-import") (part "RESISTOR_?_0805HV330K"))
    )
    (comp (ref "R40")
      (value "RESISTOR_0603_41.2K")
      (footprint "eagle-import:0603-RES")
      (fields
        (field (name "MANUFACTURER") "Panasonic Electronic Components")
        (field (name "MPN") " ERJ-PB3B4122V")
        (field (name "POWER") "0.2W")
        (field (name "RESISTANCE") "41.2k")
      )
      (libsource (lib "eagle-import") (part "RESISTOR_?_060341.2K"))
    )
    (comp (ref "R41")
      (value "RESISTOR_0603_41.2K")
      (footprint "eagle-import:0603-RES")
      (fields
        (field (name "MANUFACTURER") "Panasonic Electronic Components")
        (field (name "MPN") " ERJ-PB3B4122V")
        (field (name "POWER") "0.2W")
        (field (name "RESISTANCE") "41.2k")
      )
      (libsource (lib "eagle-import") (part "RESISTOR_?_060341.2K"))
    )
    (comp (ref "T1")
      (value "TRANSFORMER(3W)")
      (footprint "eagle-import:PQ2620")
      (fields (field (name "MPN") "11328-T061") (field (name "MANUFACTURER") "Sumida"))
      (libsource (lib "eagle-import") (part "TRANSFORMER(3W)"))
    )
    (comp (ref "TS+10V")
      (value "TEST_POINT")
      (footprint "eagle-import:5015")
      (fields (field (name "MPN") "5015") (field (name "MANUFACTURER") "Keystone Electronics"))
      (libsource (lib "eagle-import") (part "TEST_POINT"))
    )
    (comp (ref "TS+12V")
      (value "TEST_POINT")
      (footprint "eagle-import:5015")
      (fields (field (name "MPN") "5015") (field (name "MANUFACTURER") "Keystone Electronics"))
      (libsource (lib "eagle-import") (part "TEST_POINT"))
    )
    (comp (ref "TS-FUSED")
      (value "TEST_POINT")
      (footprint "eagle-import:5015")
      (fields (field (name "MPN") "5015") (field (name "MANUFACTURER") "Keystone Electronics"))
      (libsource (lib "eagle-import") (part "TEST_POINT"))
    )
    (comp (ref "TS_DIV_OUT")
      (value "TEST_POINT")
      (footprint "eagle-import:5015")
      (fields (field (name "MPN") "5015") (field (name "MANUFACTURER") "Keystone Electronics"))
      (libsource (lib "eagle-import") (part "TEST_POINT"))
    )
    (comp (ref "U1")
      (value "VOLTAGE_REGULATOR_SOT-223_10V")
      (footprint "eagle-import:SOT-223")
      (fields (field (name "MANUFACTURER") "Texas Instruments") (field (name "MPN") " LM2937IMPX-10/NOPB"))
      (libsource (lib "eagle-import") (part "VOLTAGE_REGULATOR_?_SOT-22310V"))
    )
    (comp (ref "U2")
      (value "LT8316")
      (footprint "eagle-import:TSSOP-20(16)")
      (fields (field (name "MPN") "LT8316EFE#PBF") (field (name "MANUFACTURER") "Analog Devices"))
      (libsource (lib "eagle-import") (part "LT8316"))
    )
    (comp (ref "U3")
      (value "ISO224B_AIRGAP")
      (footprint "eagle-import:SOIC-08(WIDE,0.295_)-AIRGAP")
      (fields (field (name "MANUFACTURER") "Texas Instruments") (field (name "MPN") "ISO224BDWVR"))
      (libsource (lib "eagle-import") (part "ISO224_AIRGAPB"))
    )
    (comp (ref "U4")
      (value "ISO224B_AIRGAP")
      (footprint "eagle-import:SOIC-08(WIDE,0.295_)-AIRGAP")
      (fields (field (name "MANUFACTURER") "Texas Instruments") (field (name "MPN") "ISO224BDWVR"))
      (libsource (lib "eagle-import") (part "ISO224_AIRGAPB"))
    )
  )
  (nets
    (net (code "1") (name "+5V") (class "Default")
      (node (ref "+5V") (pin "1") (pinfunction "1_1") (pintype "passive"))
      (node (ref "A1") (pin "3") (pinfunction "OUT_3") (pintype "power_in"))
      (node (ref "C19") (pin "1") (pinfunction "1_1") (pintype "passive"))
      (node (ref "C20") (pin "1") (pinfunction "1_1") (pintype "passive"))
      (node (ref "C21") (pin "1") (pinfunction "1_1") (pintype "passive"))
      (node (ref "C22") (pin "1") (pinfunction "1_1") (pintype "passive"))
      (node (ref "C23") (pin "1") (pinfunction "1_1") (pintype "passive"))
      (node (ref "C24") (pin "1") (pinfunction "1_1") (pintype "passive"))
      (node (ref "C25") (pin "1") (pinfunction "1_1") (pintype "passive"))
      (node (ref "R26") (pin "1") (pinfunction "1_1") (pintype "passive"))
      (node (ref "R35") (pin "2") (pinfunction "2_2") (pintype "passive"))
      (node (ref "U10") (pin "5") (pinfunction "V+_5") (pintype "power_in"))
      (node (ref "U3") (pin "8") (pinfunction "VDD2_8") (pintype "power_in"))
      (node (ref "U4") (pin "8") (pinfunction "VDD2_8") (pintype "power_in"))
    )
    (net (code "2") (name "+24V") (class "Default")
      (node (ref "+24V") (pin "1") (pinfunction "1_1") (pintype "passive"))
      (node (ref "A1") (pin "1") (pinfunction "IN_1") (pintype "power_in"))
      (node (ref "C26") (pin "1") (pinfunction "1_1") (pintype "passive"))
      (node (ref "C27") (pin "1") (pinfunction "1_1") (pintype "passive"))
      (node (ref "J3") (pin "1") (pinfunction "1_1") (pintype "passive"))
      (node (ref "R25") (pin "2") (pinfunction "2_2") (pintype "passive"))
    )
    (net (code "3") (name "DCDC_ENABLE") (class "Default")
      (node (ref "D7") (pin "3") (pinfunction "C_3") (pintype "passive"))
      (node (ref "R28") (pin "2") (pinfunction "2_2") (pintype "passive"))
      (node (ref "R31") (pin "2") (pinfunction "2_2") (pintype "passive"))
      (node (ref "R33") (pin "1") (pinfunction "1_1") (pintype "passive"))
      (node (ref "U10") (pin "4") (pinfunction "OUT_4") (pintype "bidirectional"))
    )
    (net (code "4") (name "GND") (class "Default")
      (node (ref "A1") (pin "2") (pinfunction "GND_2") (pintype "power_in"))
      (node (ref "C19") (pin "2") (pinfunction "2_2") (pintype "passive"))
      (node (ref "C20") (pin "2") (pinfunction "2_2") (pintype "passive"))
      (node (ref "C21") (pin "2") (pinfunction "2_2") (pintype "passive"))
      (node (ref "C22") (pin "2") (pinfunction "2_2") (pintype "passive"))
      (node (ref "C23") (pin "2") (pinfunction "2_2") (pintype "passive"))
      (node (ref "C24") (pin "2") (pinfunction "2_2") (pintype "passive"))
      (node (ref "C25") (pin "2") (pinfunction "2_2") (pintype "passive"))
      (node (ref "C26") (pin "2") (pinfunction "2_2") (pintype "passive"))
      (node (ref "C27") (pin "2") (pinfunction "2_2") (pintype "passive"))
      (node (ref "D3") (pin "1") (pinfunction "C_1") (pintype "passive"))
      (node (ref "D4") (pin "1") (pinfunction "C_1") (pintype "passive"))
      (node (ref "D5") (pin "1") (pinfunction "C_1") (pintype "passive"))
      (node (ref "D6") (pin "1") (pinfunction "C_1") (pintype "passive"))
      (node (ref "D7") (pin "1") (pinfunction "A_1") (pintype "passive"))
      (node (ref "D8") (pin "1") (pinfunction "C_1") (pintype "passive"))
      (node (ref "GND") (pin "1") (pinfunction "1_1") (pintype "passive"))
      (node (ref "J3") (pin "4") (pinfunction "4_4") (pintype "passive"))
      (node (ref "Q2") (pin "2") (pinfunction "S_2") (pintype "passive"))
      (node (ref "R28") (pin "1") (pinfunction "1_1") (pintype "passive"))
      (node (ref "R32") (pin "1") (pinfunction "1_1") (pintype "passive"))
      (node (ref "R34") (pin "1") (pinfunction "1_1") (pintype "passive"))
      (node (ref "U10") (pin "2") (pinfunction "GND_2") (pintype "power_in"))
      (node (ref "U3") (pin "5") (pinfunction "GND2_5") (pintype "power_in"))
      (node (ref "U4") (pin "5") (pinfunction "GND2_5") (pintype "power_in"))
      (node (ref "U5") (pin "2") (pinfunction "CONTROL-_2") (pintype "passive"))
    )
    (net (code "5") (name "IP+") (class "Default")
      (node (ref "IP+") (pin "1") (pinfunction "1_1") (pintype "passive"))
      (node (ref "J3") (pin "5") (pinfunction "5_5") (pintype "passive"))
      (node (ref "U4") (pin "7") (pinfunction "OUTP_7") (pintype "output"))
    )
    (net (code "6") (name "IP-") (class "Default")
      (node (ref "IP-") (pin "1") (pinfunction "1_1") (pintype "passive"))
      (node (ref "J3") (pin "6") (pinfunction "6_6") (pintype "passive"))
      (node (ref "U4") (pin "6") (pinfunction "OUTN_6") (pintype "output"))
    )
    (net (code "7") (name "IT+") (class "Default")
      (node (ref "IT+") (pin "1") (pinfunction "1_1") (pintype "passive"))
      (node (ref "J3") (pin "7") (pinfunction "7_7") (pintype "passive"))
      (node (ref "U3") (pin "7") (pinfunction "OUTP_7") (pintype "output"))
    )
    (net (code "8") (name "IT-") (class "Default")
      (node (ref "IT-") (pin "1") (pinfunction "1_1") (pintype "passive"))
      (node (ref "J3") (pin "8") (pinfunction "8_8") (pintype "passive"))
      (node (ref "U3") (pin "6") (pinfunction "OUTN_6") (pintype "output"))
    )
    (net (code "9") (name "LED+") (class "Default")
      (node (ref "J2") (pin "3") (pinfunction "3_3") (pintype "passive"))
      (node (ref "R20") (pin "2") (pinfunction "2_2") (pintype "passive"))
    )
    (net (code "10") (name "Net-(C2-Pad2)") (class "Default")
      (node (ref "C2") (pin "2") (pinfunction "2_2") (pintype "passive"))
      (node (ref "R3") (pin "2") (pinfunction "2_2") (pintype "passive"))
    )
    (net (code "11") (name "Net-(C9-Pad1)") (class "Default")
      (node (ref "C9") (pin "1") (pinfunction "1_1") (pintype "passive"))
      (node (ref "R7") (pin "1") (pinfunction "1_1") (pintype "passive"))
    )
    (net (code "12") (name "Net-(CV1-Pad2)") (class "Default")
      (node (ref "CV1") (pin "2") (pinfunction "2_2") (pintype "passive"))
      (node (ref "R36") (pin "2") (pinfunction "2_2") (pintype "passive"))
    )
    (net (code "13") (name "Net-(D1-A)") (class "Default")
      (node (ref "C2") (pin "1") (pinfunction "1_1") (pintype "passive"))
      (node (ref "D1") (pin "1") (pinfunction "A_1") (pintype "passive"))
      (node (ref "R5") (pin "2") (pinfunction "2_2") (pintype "passive"))
      (node (ref "T1") (pin "5") (pinfunction "5_5") (pintype "bidirectional"))
    )
    (net (code "14") (name "Net-(D1-C)") (class "Default")
      (node (ref "C4") (pin "1") (pinfunction "1_1") (pintype "passive"))
      (node (ref "D1") (pin "2") (pinfunction "C_2") (pintype "passive"))
      (node (ref "U2") (pin "9") (pinfunction "BIAS_9") (pintype "bidirectional"))
    )
    (net (code "15") (name "Net-(D3-A)") (class "Default")
      (node (ref "D3") (pin "2") (pinfunction "A_2") (pintype "passive"))
      (node (ref "R25") (pin "1") (pinfunction "1_1") (pintype "passive"))
    )
    (net (code "16") (name "Net-(D4-A)") (class "Default")
      (node (ref "D4") (pin "2") (pinfunction "A_2") (pintype "passive"))
      (node (ref "R26") (pin "2") (pinfunction "2_2") (pintype "passive"))
    )
    (net (code "17") (name "Net-(D5-A)") (class "Default")
      (node (ref "D5") (pin "2") (pinfunction "A_2") (pintype "passive"))
      (node (ref "R27") (pin "1") (pinfunction "1_1") (pintype "passive"))
    )
    (net (code "18") (name "Net-(D6-A)") (class "Default")
      (node (ref "D6") (pin "2") (pinfunction "A_2") (pintype "passive"))
      (node (ref "R29") (pin "1") (pinfunction "1_1") (pintype "passive"))
    )
    (net (code "19") (name "Net-(D8-A)") (class "Default")
      (node (ref "D8") (pin "2") (pinfunction "A_2") (pintype "passive"))
      (node (ref "R31") (pin "1") (pinfunction "1_1") (pintype "passive"))
    )
    (net (code "20") (name "Net-(D101-A)") (class "Default")
      (node (ref "D101") (pin "1") (pinfunction "A_1") (pintype "passive"))
      (node (ref "R36") (pin "1") (pinfunction "1_1") (pintype "passive"))
      (node (ref "T1") (pin "8") (pinfunction "8,9_8") (pintype "bidirectional"))
      (node (ref "T1") (pin "9") (pinfunction "8,9_9") (pintype "bidirectional"))
    )
    (net (code "21") (name "Net-(D102-C)") (class "Default")
      (node (ref "D102") (pin "2") (pinfunction "C_2") (pintype "passive"))
      (node (ref "D103") (pin "C") (pinfunction "C_C") (pintype "passive"))
    )
    (net (code "22") (name "Net-(D103-PadA)") (class "Default")
      (node (ref "D103") (pin "A") (pinfunction "A_A") (pintype "passive"))
      (node (ref "Q1") (pin "D") (pinfunction "D_D") (pintype "passive"))
      (node (ref "T1") (pin "1") (pinfunction "1_1") (pintype "bidirectional"))
    )
    (net (code "23") (name "Net-(K1-COIL-)") (class "Default")
      (node (ref "D100") (pin "A") (pinfunction "A_A") (pintype "passive"))
      (node (ref "K1") (pin "3") (pinfunction "COIL-_3") (pintype "bidirectional"))
      (node (ref "Q2") (pin "3") (pinfunction "D_3") (pintype "passive"))
    )
    (net (code "24") (name "Net-(K1-CONTACT2)") (class "Default")
      (node (ref "K1") (pin "1") (pinfunction "CONTACT2_1") (pintype "bidirectional"))
      (node (ref "R13") (pin "1") (pinfunction "1_1") (pintype "passive"))
      (node (ref "R23") (pin "1") (pinfunction "1_1") (pintype "passive"))
    )
    (net (code "25") (name "Net-(LED_+12V-A)") (class "Default")
      (node (ref "LED_+12V") (pin "2") (pinfunction "A_2") (pintype "passive"))
      (node (ref "R1") (pin "1") (pinfunction "1_1") (pintype "passive"))
    )
    (net (code "26") (name "Net-(Q1-PadG)") (class "Default")
      (node (ref "Q1") (pin "G") (pinfunction "G_G") (pintype "passive"))
      (node (ref "R4") (pin "2") (pinfunction "2_2") (pintype "passive"))
    )
    (net (code "27") (name "Net-(Q2-G)") (class "Default")
      (node (ref "Q2") (pin "1") (pinfunction "G_1") (pintype "passive"))
      (node (ref "R33") (pin "2") (pinfunction "2_2") (pintype "passive"))
    )
    (net (code "28") (name "Net-(R10-Pad2)") (class "Default")
      (node (ref "R10") (pin "2") (pinfunction "2_2") (pintype "passive"))
      (node (ref "R11") (pin "1") (pinfunction "1_1") (pintype "passive"))
    )
    (net (code "29") (name "Net-(R11-Pad2)") (class "Default")
      (node (ref "R11") (pin "2") (pinfunction "2_2") (pintype "passive"))
      (node (ref "R9") (pin "1") (pinfunction "1_1") (pintype "passive"))
    )
    (net (code "30") (name "Net-(R19-Pad2)") (class "Default")
      (node (ref "R19") (pin "2") (pinfunction "2_2") (pintype "passive"))
      (node (ref "R21") (pin "1") (pinfunction "1_1") (pintype "passive"))
    )
    (net (code "31") (name "Net-(R21-Pad2)") (class "Default")
      (node (ref "R21") (pin "2") (pinfunction "2_2") (pintype "passive"))
      (node (ref "R22") (pin "1") (pinfunction "1_1") (pintype "passive"))
    )
    (net (code "32") (name "Net-(R37-Pad2)") (class "Default")
      (node (ref "R37") (pin "2") (pinfunction "2_2") (pintype "passive"))
      (node (ref "R38") (pin "1") (pinfunction "1_1") (pintype "passive"))
    )
    (net (code "33") (name "Net-(R38-Pad2)") (class "Default")
      (node (ref "R38") (pin "2") (pinfunction "2_2") (pintype "passive"))
      (node (ref "R39") (pin "1") (pinfunction "1_1") (pintype "passive"))
    )
    (net (code "34") (name "Net-(U2-DCM)") (class "Default")
      (node (ref "R3") (pin "1") (pinfunction "1_1") (pintype "passive"))
      (node (ref "U2") (pin "10") (pinfunction "DCM_10") (pintype "bidirectional"))
    )
    (net (code "35") (name "Net-(U2-EN{slash}UVLO)") (class "Default")
      (node (ref "R39") (pin "2") (pinfunction "2_2") (pintype "passive"))
      (node (ref "R40") (pin "2") (pinfunction "2_2") (pintype "passive"))
      (node (ref "R41") (pin "2") (pinfunction "2_2") (pintype "passive"))
      (node (ref "U2") (pin "17") (pinfunction "EN/UVLO_17") (pintype "bidirectional"))
    )
    (net (code "36") (name "Net-(U2-FB)") (class "Default")
      (node (ref "R5") (pin "1") (pinfunction "1_1") (pintype "passive"))
      (node (ref "R6") (pin "2") (pinfunction "2_2") (pintype "passive"))
      (node (ref "U2") (pin "12") (pinfunction "FB_12") (pintype "bidirectional"))
    )
    (net (code "37") (name "Net-(U2-GATE)") (class "Default")
      (node (ref "R4") (pin "1") (pinfunction "1_1") (pintype "passive"))
      (node (ref "U2") (pin "19") (pinfunction "GATE_19") (pintype "bidirectional"))
    )
    (net (code "38") (name "Net-(U2-INTVCC)") (class "Default")
      (node (ref "C6") (pin "1") (pinfunction "1_1") (pintype "passive"))
      (node (ref "U2") (pin "8") (pinfunction "INTVCC_8") (pintype "bidirectional"))
    )
    (net (code "39") (name "Net-(U2-IREG)") (class "Default")
      (node (ref "R12") (pin "2") (pinfunction "2_2") (pintype "passive"))
      (node (ref "U2") (pin "14") (pinfunction "IREG_14") (pintype "bidirectional"))
    )
    (net (code "40") (name "Net-(U2-SENSE)") (class "Default")
      (node (ref "Q1") (pin "S") (pinfunction "S_S") (pintype "passive"))
      (node (ref "R2") (pin "2") (pinfunction "2_2") (pintype "passive"))
      (node (ref "U2") (pin "18") (pinfunction "SENSE_18") (pintype "bidirectional"))
    )
    (net (code "41") (name "Net-(U2-VC)") (class "Default")
      (node (ref "R7") (pin "2") (pinfunction "2_2") (pintype "passive"))
      (node (ref "U2") (pin "13") (pinfunction "VC_13") (pintype "bidirectional"))
    )
    (net (code "42") (name "Net-(U3-IN)") (class "Default")
      (node (ref "C12") (pin "1") (pinfunction "1_1") (pintype "passive"))
      (node (ref "R15") (pin "2") (pinfunction "2_2") (pintype "passive"))
      (node (ref "U3") (pin "2") (pinfunction "IN_2") (pintype "input"))
    )
    (net (code "43") (name "Net-(U3-VCAP)") (class "Default")
      (node (ref "C16") (pin "1") (pinfunction "1_1") (pintype "passive"))
      (node (ref "U3") (pin "1") (pinfunction "VCAP_1") (pintype "passive"))
    )
    (net (code "44") (name "Net-(U4-IN)") (class "Default")
      (node (ref "C10") (pin "1") (pinfunction "1_1") (pintype "passive"))
      (node (ref "R18") (pin "2") (pinfunction "2_2") (pintype "passive"))
      (node (ref "U4") (pin "2") (pinfunction "IN_2") (pintype "input"))
    )
    (net (code "45") (name "Net-(U4-VCAP)") (class "Default")
      (node (ref "C17") (pin "1") (pinfunction "1_1") (pintype "passive"))
      (node (ref "U4") (pin "1") (pinfunction "VCAP_1") (pintype "passive"))
    )
    (net (code "46") (name "Net-(U5-CONTACT1)") (class "Default")
      (node (ref "R24") (pin "1") (pinfunction "1_1") (pintype "passive"))
      (node (ref "U5") (pin "3") (pinfunction "CONTACT1_3") (pintype "bidirectional"))
    )
    (net (code "47") (name "Net-(U5-CONTROL+)") (class "Default")
      (node (ref "R30") (pin "2") (pinfunction "2_2") (pintype "passive"))
      (node (ref "U5") (pin "1") (pinfunction "CONTROL+_1") (pintype "passive"))
    )
    (net (code "48") (name "Net-(U10-DIV)") (class "Default")
      (node (ref "R34") (pin "2") (pinfunction "2_2") (pintype "passive"))
      (node (ref "R35") (pin "1") (pinfunction "1_1") (pintype "passive"))
      (node (ref "U10") (pin "6") (pinfunction "DIV_6") (pintype "bidirectional"))
    )
    (net (code "49") (name "Net-(U10-SET)") (class "Default")
      (node (ref "R32") (pin "2") (pinfunction "2_2") (pintype "passive"))
      (node (ref "U10") (pin "3") (pinfunction "SET_3") (pintype "bidirectional"))
    )
    (net (code "50") (name "PACK+") (class "Default")
      (node (ref "J1") (pin "5") (pinfunction "5_5") (pintype "passive"))
      (node (ref "K1") (pin "2") (pinfunction "CONTACT1_2") (pintype "bidirectional"))
      (node (ref "PACK+") (pin "1") (pinfunction "1_1") (pintype "passive"))
      (node (ref "U5") (pin "4") (pinfunction "CONTACT2_4") (pintype "bidirectional"))
    )
    (net (code "51") (name "PACK+FUSED") (class "Default")
      (node (ref "PACK+FUSED") (pin "1") (pinfunction "1_1") (pintype "passive"))
      (node (ref "R22") (pin "2") (pinfunction "2_2") (pintype "passive"))
      (node (ref "R24") (pin "2") (pinfunction "2_2") (pintype "passive"))
    )
    (net (code "52") (name "PACK_DIV_OUT") (class "Default")
      (node (ref "PACK_DIV_OUT") (pin "1") (pinfunction "1_1") (pintype "passive"))
      (node (ref "R16") (pin "2") (pinfunction "2_2") (pintype "passive"))
      (node (ref "R17") (pin "2") (pinfunction "2_2") (pintype "passive"))
      (node (ref "R18") (pin "1") (pinfunction "1_1") (pintype "passive"))
      (node (ref "R19") (pin "1") (pinfunction "1_1") (pintype "passive"))
    )
    (net (code "53") (name "PRECHARGE_OK") (class "Default")
      (node (ref "J3") (pin "3") (pinfunction "3_3") (pintype "passive"))
      (node (ref "PRECHARGE_OK") (pin "1") (pinfunction "1_1") (pintype "passive"))
      (node (ref "R29") (pin "2") (pinfunction "2_2") (pintype "passive"))
      (node (ref "U10") (pin "1") (pinfunction "IN_1") (pintype "bidirectional"))
    )
    (net (code "54") (name "SHDN") (class "Default")
      (node (ref "D100") (pin "C") (pinfunction "C_C") (pintype "passive"))
      (node (ref "J3") (pin "2") (pinfunction "2_2") (pintype "passive"))
      (node (ref "K1") (pin "4") (pinfunction "COIL+_4") (pintype "bidirectional"))
      (node (ref "R27") (pin "2") (pinfunction "2_2") (pintype "passive"))
      (node (ref "R30") (pin "1") (pinfunction "1_1") (pintype "passive"))
      (node (ref "SHDN") (pin "1") (pinfunction "1_1") (pintype "passive"))
    )
    (net (code "55") (name "TS+10V") (class "Default")
      (node (ref "C11") (pin "1") (pinfunction "1_1") (pintype "passive"))
      (node (ref "C13") (pin "1") (pinfunction "1_1") (pintype "passive"))
      (node (ref "C15") (pin "1") (pinfunction "1_1") (pintype "passive"))
      (node (ref "C18") (pin "1") (pinfunction "1_1") (pintype "passive"))
      (node (ref "C5") (pin "1") (pinfunction "1_1") (pintype "passive"))
      (node (ref "TS+10V") (pin "1") (pinfunction "1_1") (pintype "passive"))
      (node (ref "U1") (pin "2") (pinfunction "OUT_2") (pintype "power_in"))
      (node (ref "U1") (pin "4") (pinfunction "OUT_4") (pintype "power_in"))
      (node (ref "U3") (pin "3") (pinfunction "VDD1_3") (pintype "power_in"))
      (node (ref "U4") (pin "3") (pinfunction "VDD1_3") (pintype "power_in"))
    )
    (net (code "56") (name "TS+12V") (class "Default")
      (node (ref "C1") (pin "1") (pinfunction "1_1") (pintype "passive"))
      (node (ref "C28") (pin "PLUS") (pinfunction "PLUS_PLUS") (pintype "passive"))
      (node (ref "C7") (pin "1") (pinfunction "1_1") (pintype "passive"))
      (node (ref "C8") (pin "1") (pinfunction "1_1") (pintype "passive"))
      (node (ref "CV1") (pin "1") (pinfunction "1_1") (pintype "passive"))
      (node (ref "D101") (pin "2") (pinfunction "C_2") (pintype "passive"))
      (node (ref "R1") (pin "2") (pinfunction "2_2") (pintype "passive"))
      (node (ref "R20") (pin "1") (pinfunction "1_1") (pintype "passive"))
      (node (ref "TS+12V") (pin "1") (pinfunction "1_1") (pintype "passive"))
      (node (ref "U1") (pin "3") (pinfunction "IN_3") (pintype "power_in"))
    )
    (net (code "57") (name "TS+FUSED") (class "Default")
      (node (ref "C14") (pin "1") (pinfunction "1_1") (pintype "passive"))
      (node (ref "D102") (pin "1") (pinfunction "A_1") (pintype "passive"))
      (node (ref "F1") (pin "3") (pinfunction "2_3") (pintype "passive"))
      (node (ref "F1") (pin "4") (pinfunction "2_4") (pintype "passive"))
      (node (ref "J1") (pin "4") (pinfunction "4_4") (pintype "passive"))
      (node (ref "R37") (pin "1") (pinfunction "1_1") (pintype "passive"))
      (node (ref "R9") (pin "2") (pinfunction "2_2") (pintype "passive"))
      (node (ref "T1") (pin "3") (pinfunction "3_3") (pintype "bidirectional"))
      (node (ref "U2") (pin "1") (pinfunction "VIN_1") (pintype "input"))
      (node (ref "U2") (pin "2") (pinfunction "VIN_2") (pintype "input"))
      (node (ref "U2") (pin "3") (pinfunction "VIN_3") (pintype "input"))
    )
    (net (code "58") (name "TS+UNFUSED") (class "Default")
      (node (ref "F1") (pin "1") (pinfunction "1_1") (pintype "passive"))
      (node (ref "F1") (pin "2") (pinfunction "1_2") (pintype "passive"))
      (node (ref "J1") (pin "1") (pinfunction "1_1") (pintype "passive"))
      (node (ref "J1") (pin "2") (pinfunction "2_2") (pintype "passive"))
      (node (ref "R13") (pin "2") (pinfunction "2_2") (pintype "passive"))
      (node (ref "R23") (pin "2") (pinfunction "2_2") (pintype "passive"))
    )
    (net (code "59") (name "TS-FUSED") (class "Default")
      (node (ref "C1") (pin "2") (pinfunction "2_2") (pintype "passive"))
      (node (ref "C10") (pin "2") (pinfunction "2_2") (pintype "passive"))
      (node (ref "C11") (pin "2") (pinfunction "2_2") (pintype "passive"))
      (node (ref "C12") (pin "2") (pinfunction "2_2") (pintype "passive"))
      (node (ref "C13") (pin "2") (pinfunction "2_2") (pintype "passive"))
      (node (ref "C14") (pin "2") (pinfunction "2_2") (pintype "passive"))
      (node (ref "C15") (pin "2") (pinfunction "2_2") (pintype "passive"))
      (node (ref "C16") (pin "2") (pinfunction "2_2") (pintype "passive"))
      (node (ref "C17") (pin "2") (pinfunction "2_2") (pintype "passive"))
      (node (ref "C18") (pin "2") (pinfunction "2_2") (pintype "passive"))
      (node (ref "C28") (pin "MINUS") (pinfunction "MINUS_MINUS") (pintype "passive"))
      (node (ref "C4") (pin "2") (pinfunction "2_2") (pintype "passive"))
      (node (ref "C5") (pin "2") (pinfunction "2_2") (pintype "passive"))
      (node (ref "C6") (pin "2") (pinfunction "2_2") (pintype "passive"))
      (node (ref "C7") (pin "2") (pinfunction "2_2") (pintype "passive"))
      (node (ref "C8") (pin "2") (pinfunction "2_2") (pintype "passive"))
      (node (ref "C9") (pin "2") (pinfunction "2_2") (pintype "passive"))
      (node (ref "F2") (pin "3") (pinfunction "2_3") (pintype "passive"))
      (node (ref "F2") (pin "4") (pinfunction "2_4") (pintype "passive"))
      (node (ref "J2") (pin "1") (pinfunction "1_1") (pintype "passive"))
      (node (ref "J2") (pin "2") (pinfunction "2_2") (pintype "passive"))
      (node (ref "LED_+12V") (pin "1") (pinfunction "C_1") (pintype "passive"))
      (node (ref "R12") (pin "1") (pinfunction "1_1") (pintype "passive"))
      (node (ref "R14") (pin "1") (pinfunction "1_1") (pintype "passive"))
      (node (ref "R16") (pin "1") (pinfunction "1_1") (pintype "passive"))
      (node (ref "R17") (pin "1") (pinfunction "1_1") (pintype "passive"))
      (node (ref "R2") (pin "1") (pinfunction "1_1") (pintype "passive"))
      (node (ref "R40") (pin "1") (pinfunction "1_1") (pintype "passive"))
      (node (ref "R41") (pin "1") (pinfunction "1_1") (pintype "passive"))
      (node (ref "R6") (pin "1") (pinfunction "1_1") (pintype "passive"))
      (node (ref "R8") (pin "1") (pinfunction "1_1") (pintype "passive"))
      (node (ref "T1") (pin "10") (pinfunction "10,11_10") (pintype "bidirectional"))
      (node (ref "T1") (pin "11") (pinfunction "10,11_11") (pintype "bidirectional"))
      (node (ref "T1") (pin "6") (pinfunction "6_6") (pintype "bidirectional"))
      (node (ref "TS-FUSED") (pin "1") (pinfunction "1_1") (pintype "passive"))
      (node (ref "U1") (pin "1") (pinfunction "GND_1") (pintype "power_in"))
      (node (ref "U2") (pin "15") (pinfunction "GND_15") (pintype "bidirectional"))
      (node (ref "U2") (pin "16") (pinfunction "SMODE_16") (pintype "bidirectional"))
      (node (ref "U2") (pin "20") (pinfunction "GND_20") (pintype "bidirectional"))
      (node (ref "U2") (pin "THERMAL") (pinfunction "P$1_THERMAL") (pintype "output"))
      (node (ref "U3") (pin "4") (pinfunction "GND1_4") (pintype "power_in"))
      (node (ref "U4") (pin "4") (pinfunction "GND1_4") (pintype "power_in"))
    )
    (net (code "60") (name "TS-UNFUSED") (class "Default")
      (node (ref "F2") (pin "1") (pinfunction "1_1") (pintype "passive"))
      (node (ref "F2") (pin "2") (pinfunction "1_2") (pintype "passive"))
      (node (ref "J2") (pin "5") (pinfunction "5_5") (pintype "passive"))
      (node (ref "TS-UNFUSED") (pin "1") (pinfunction "1_1") (pintype "passive"))
    )
    (net (code "61") (name "TS_DIV_OUT") (class "Default")
      (node (ref "R10") (pin "1") (pinfunction "1_1") (pintype "passive"))
      (node (ref "R14") (pin "2") (pinfunction "2_2") (pintype "passive"))
      (node (ref "R15") (pin "1") (pinfunction "1_1") (pintype "passive"))
      (node (ref "R8") (pin "2") (pinfunction "2_2") (pintype "passive"))
      (node (ref "TS_DIV_OUT") (pin "1") (pinfunction "1_1") (pintype "passive"))
    )
    (net (code "62") (name "unconnected-(J1-Pad3)") (class "Default")
      (node (ref "J1") (pin "3") (pinfunction "3_3") (pintype "passive"))
    )
    (net (code "63") (name "unconnected-(J2-Pad4)") (class "Default")
      (node (ref "J2") (pin "4") (pinfunction "4_4") (pintype "passive"))
    )
    (net (code "64") (name "unconnected-(U2-TC-Pad11)") (class "Default")
      (node (ref "U2") (pin "11") (pinfunction "TC_11") (pintype "bidirectional"))
    )
  )
)
